# SchematicControlPlotter.net
KiCad netlist of a schematic drawn in EAGLE
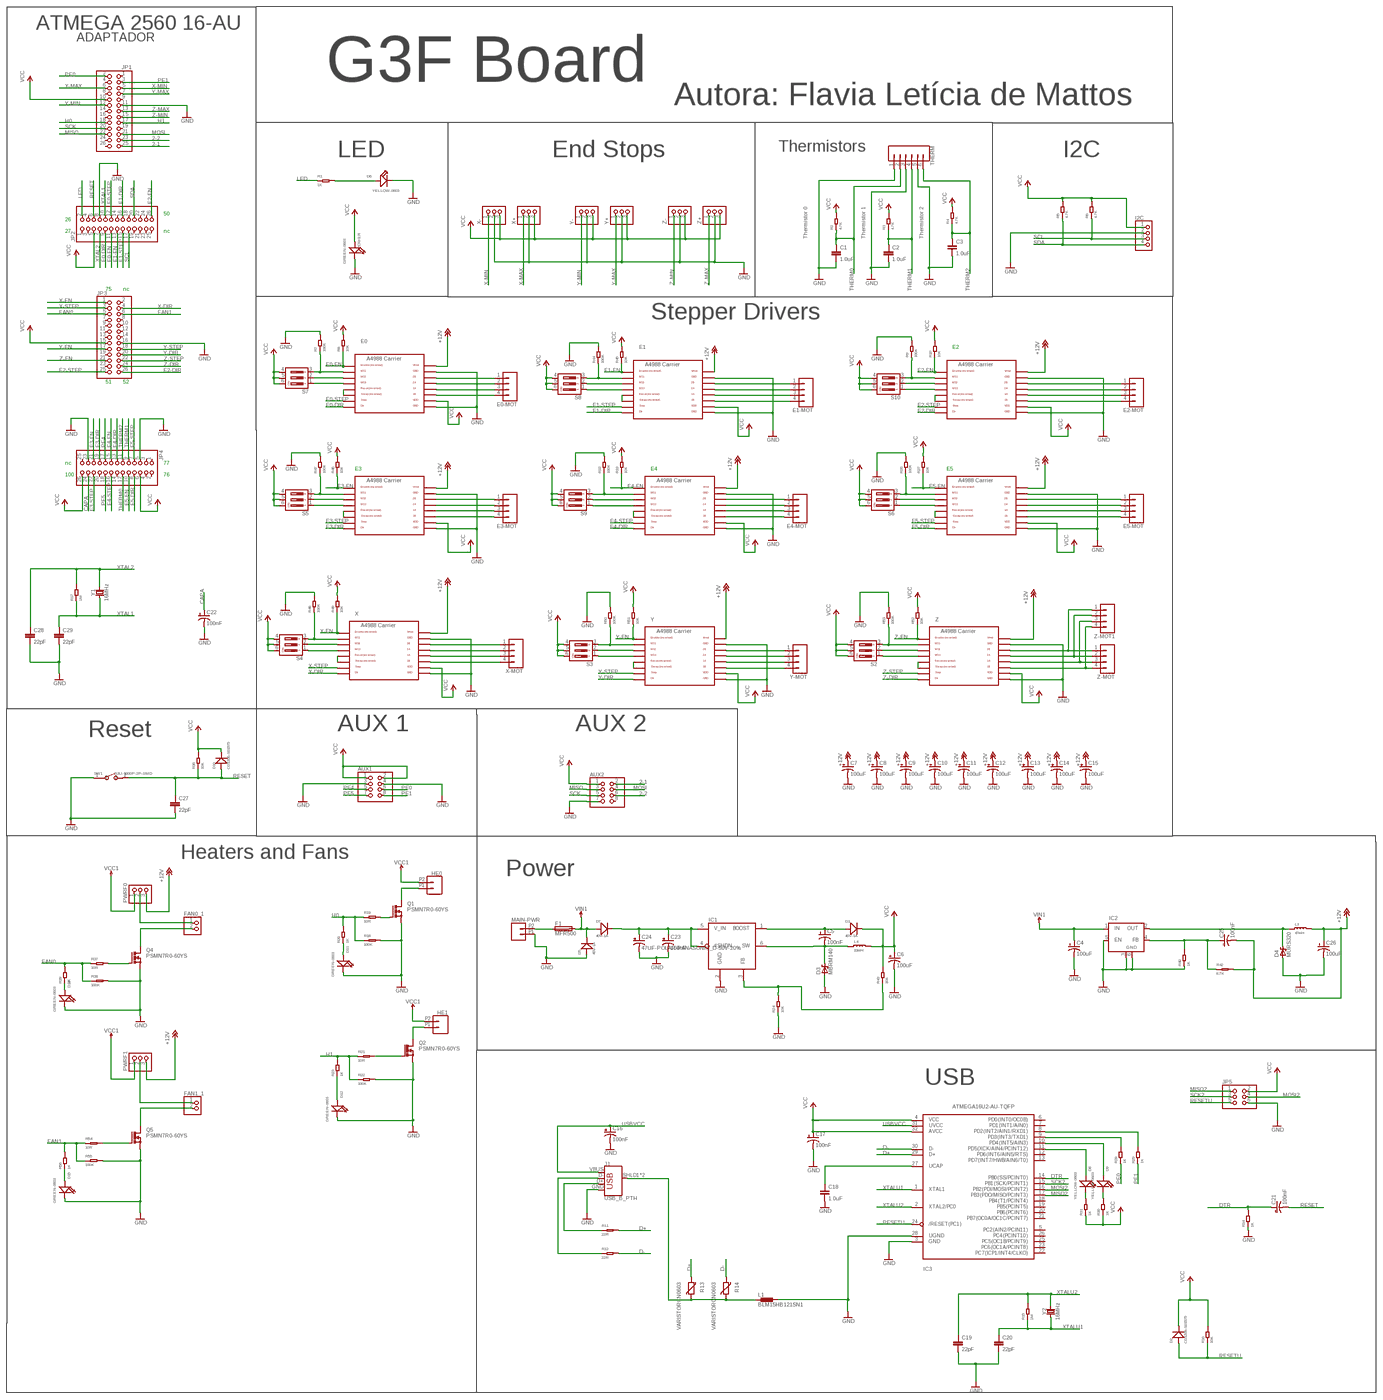
[diagram p0: schematic, sheet 1, overview]
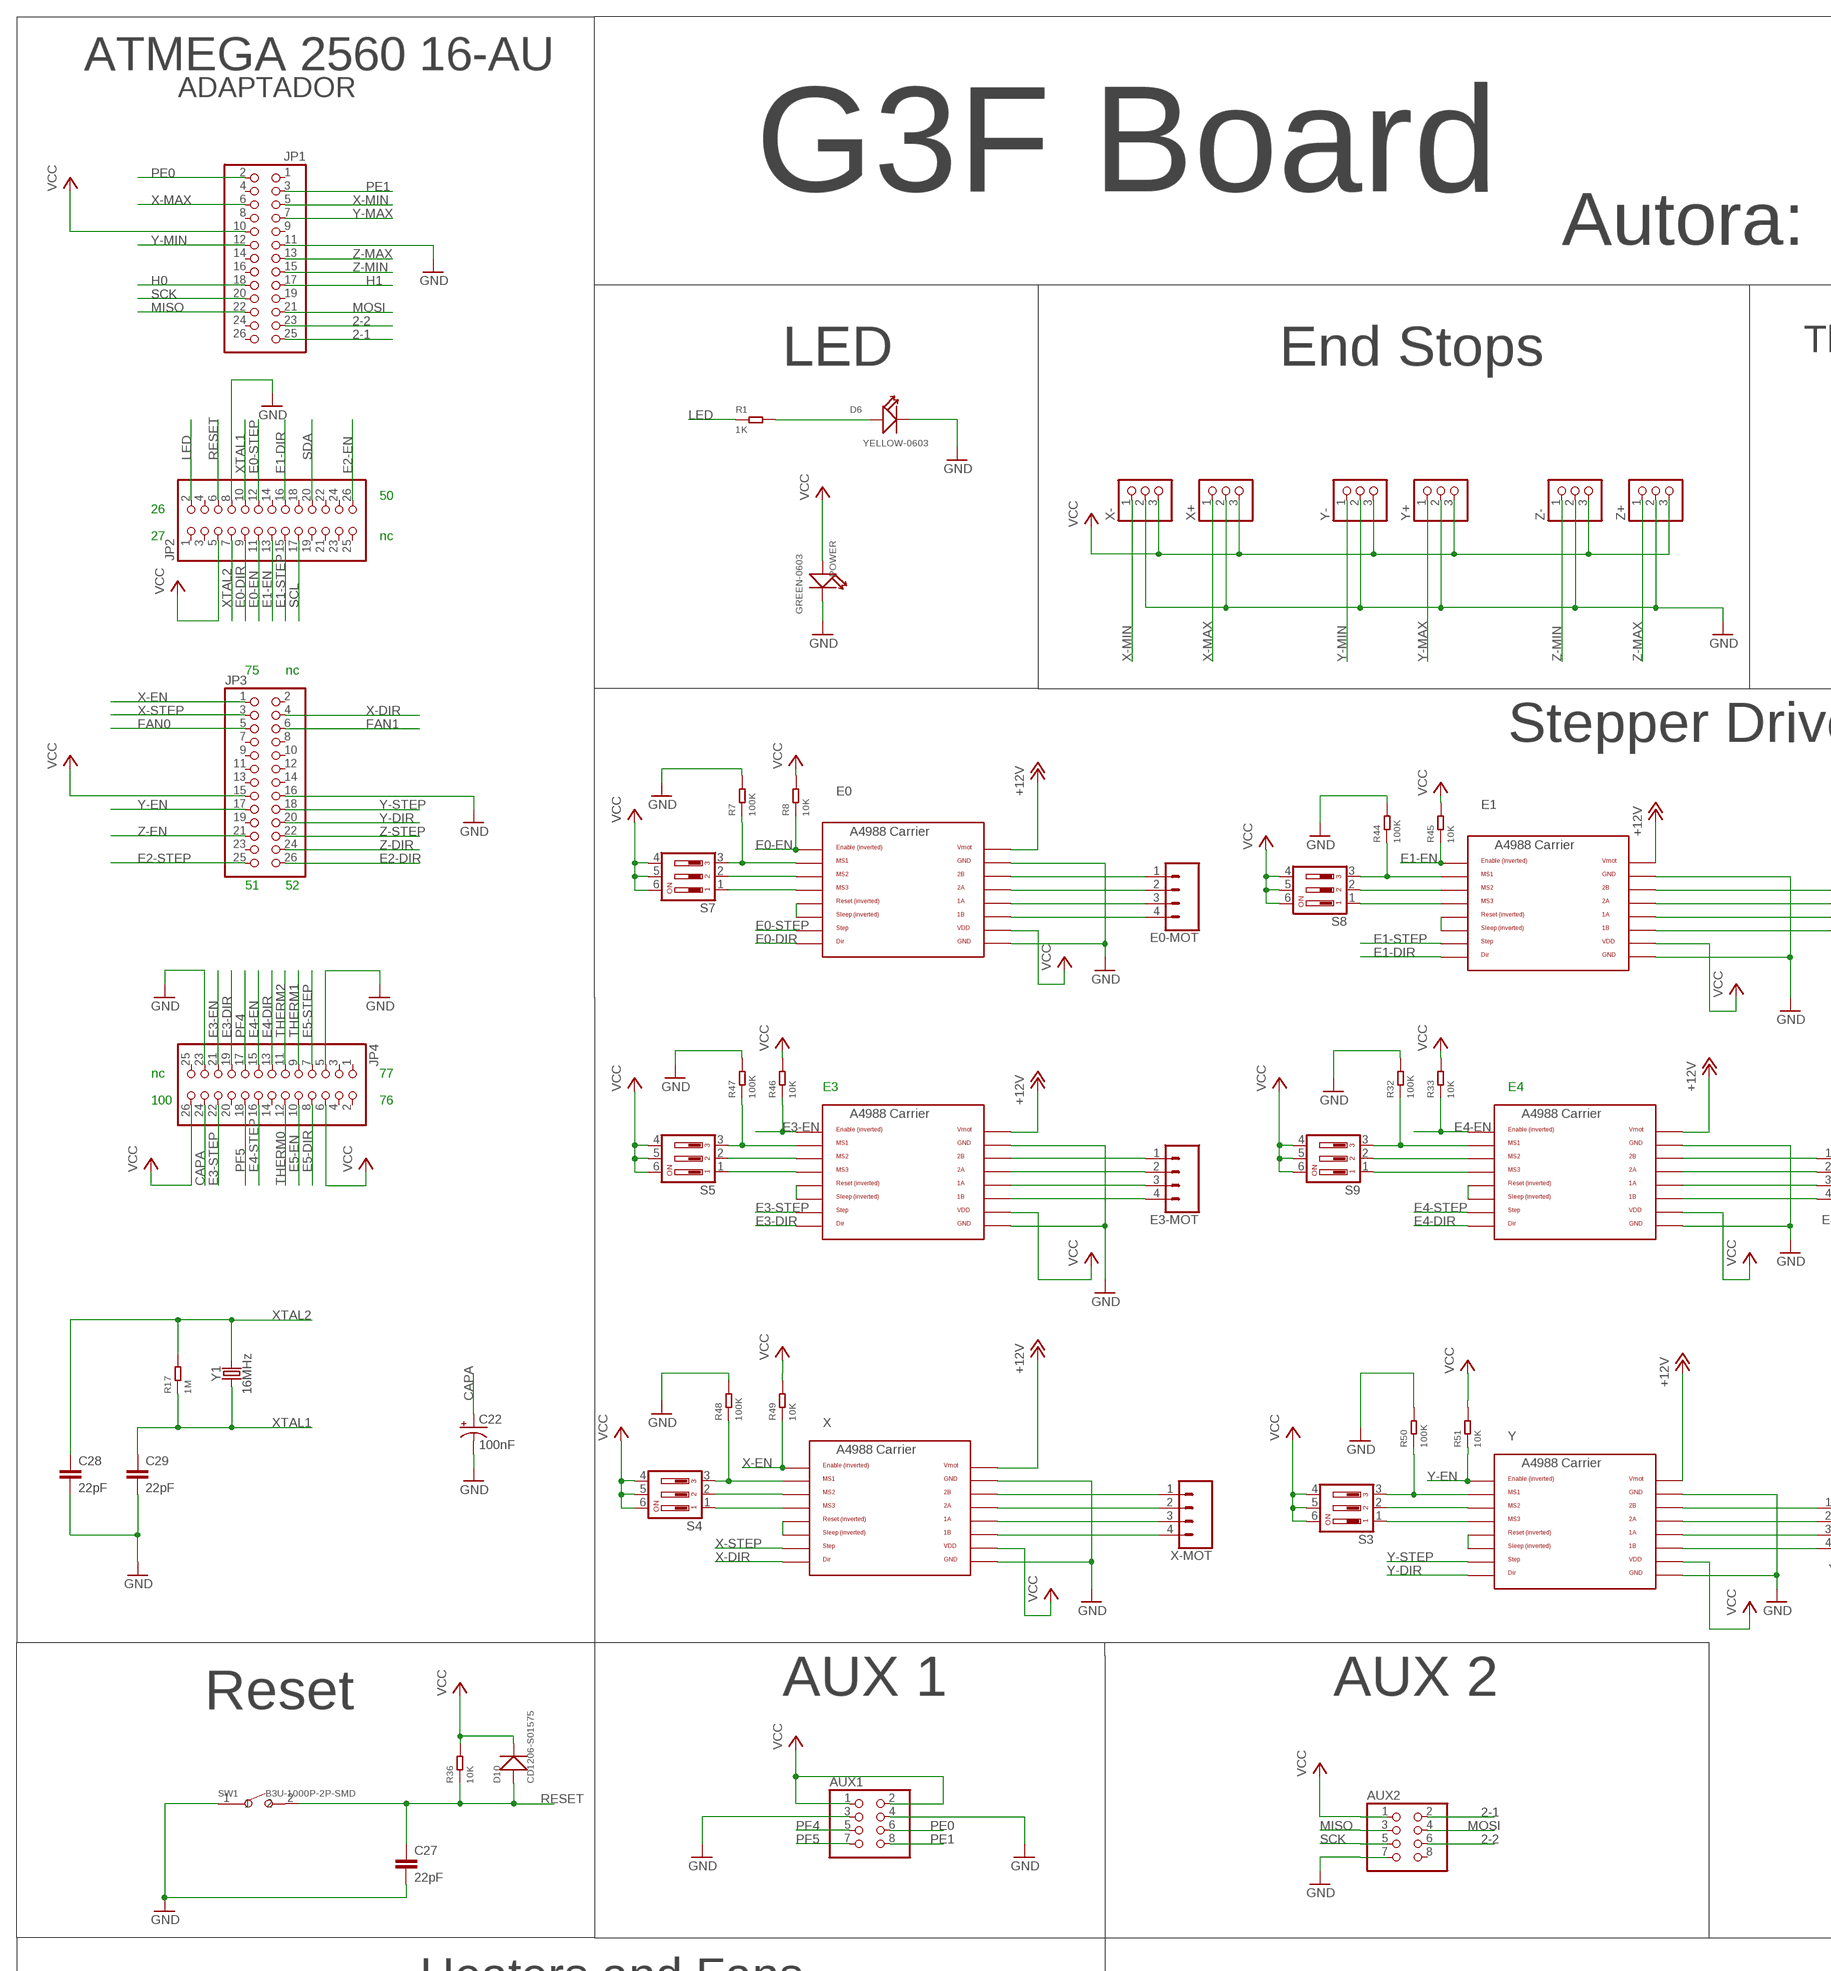
[diagram p1: schematic, sheet 1, part 1 of 4]
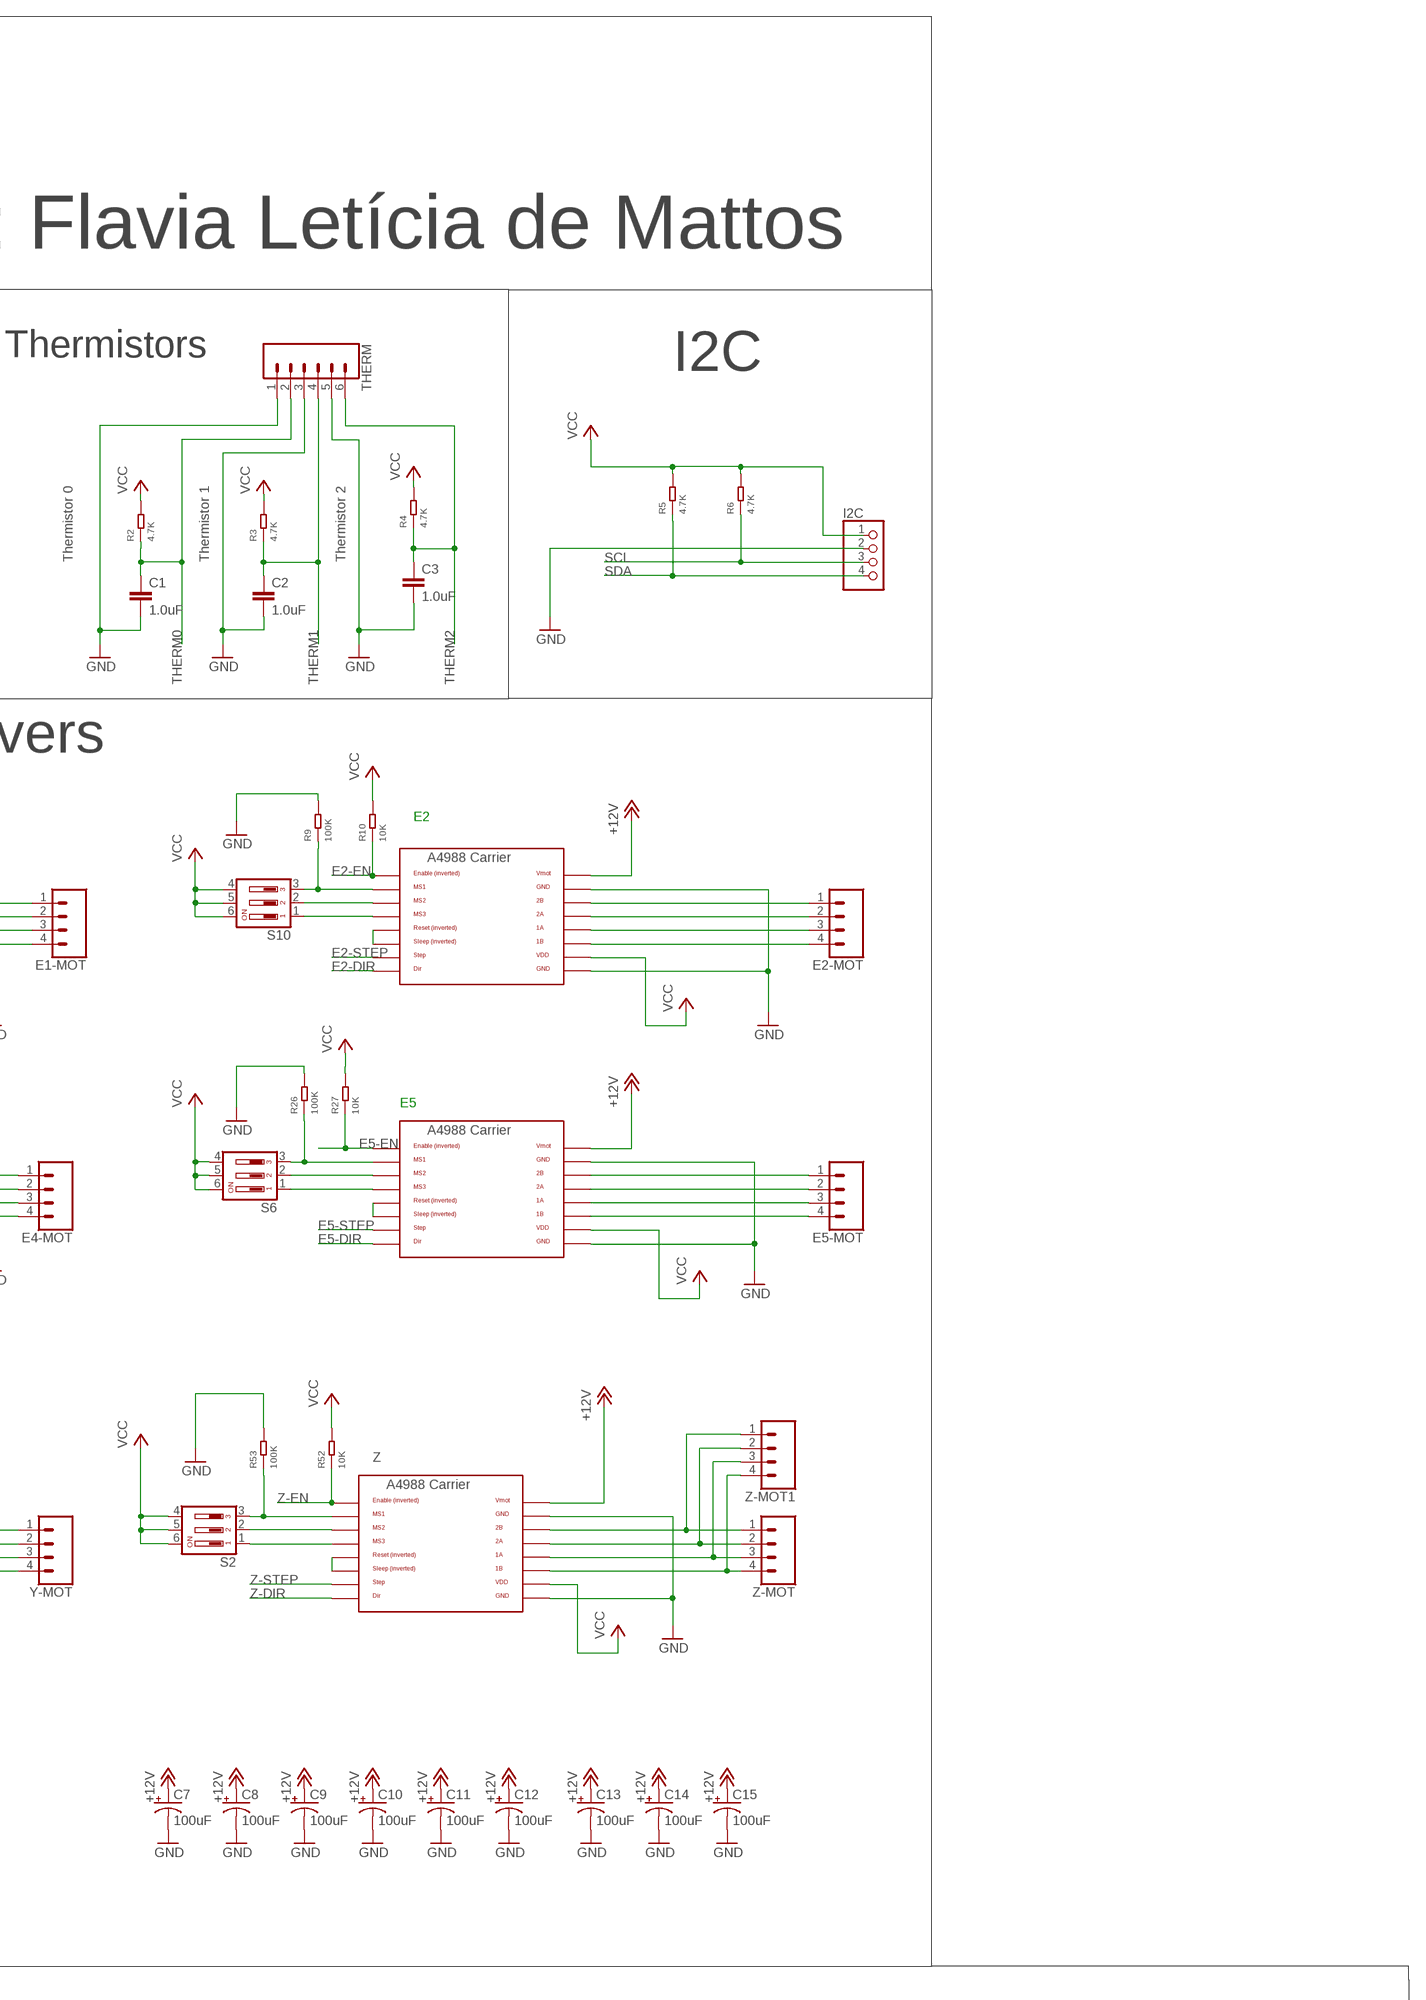
[diagram p2: schematic, sheet 1, part 2 of 4]
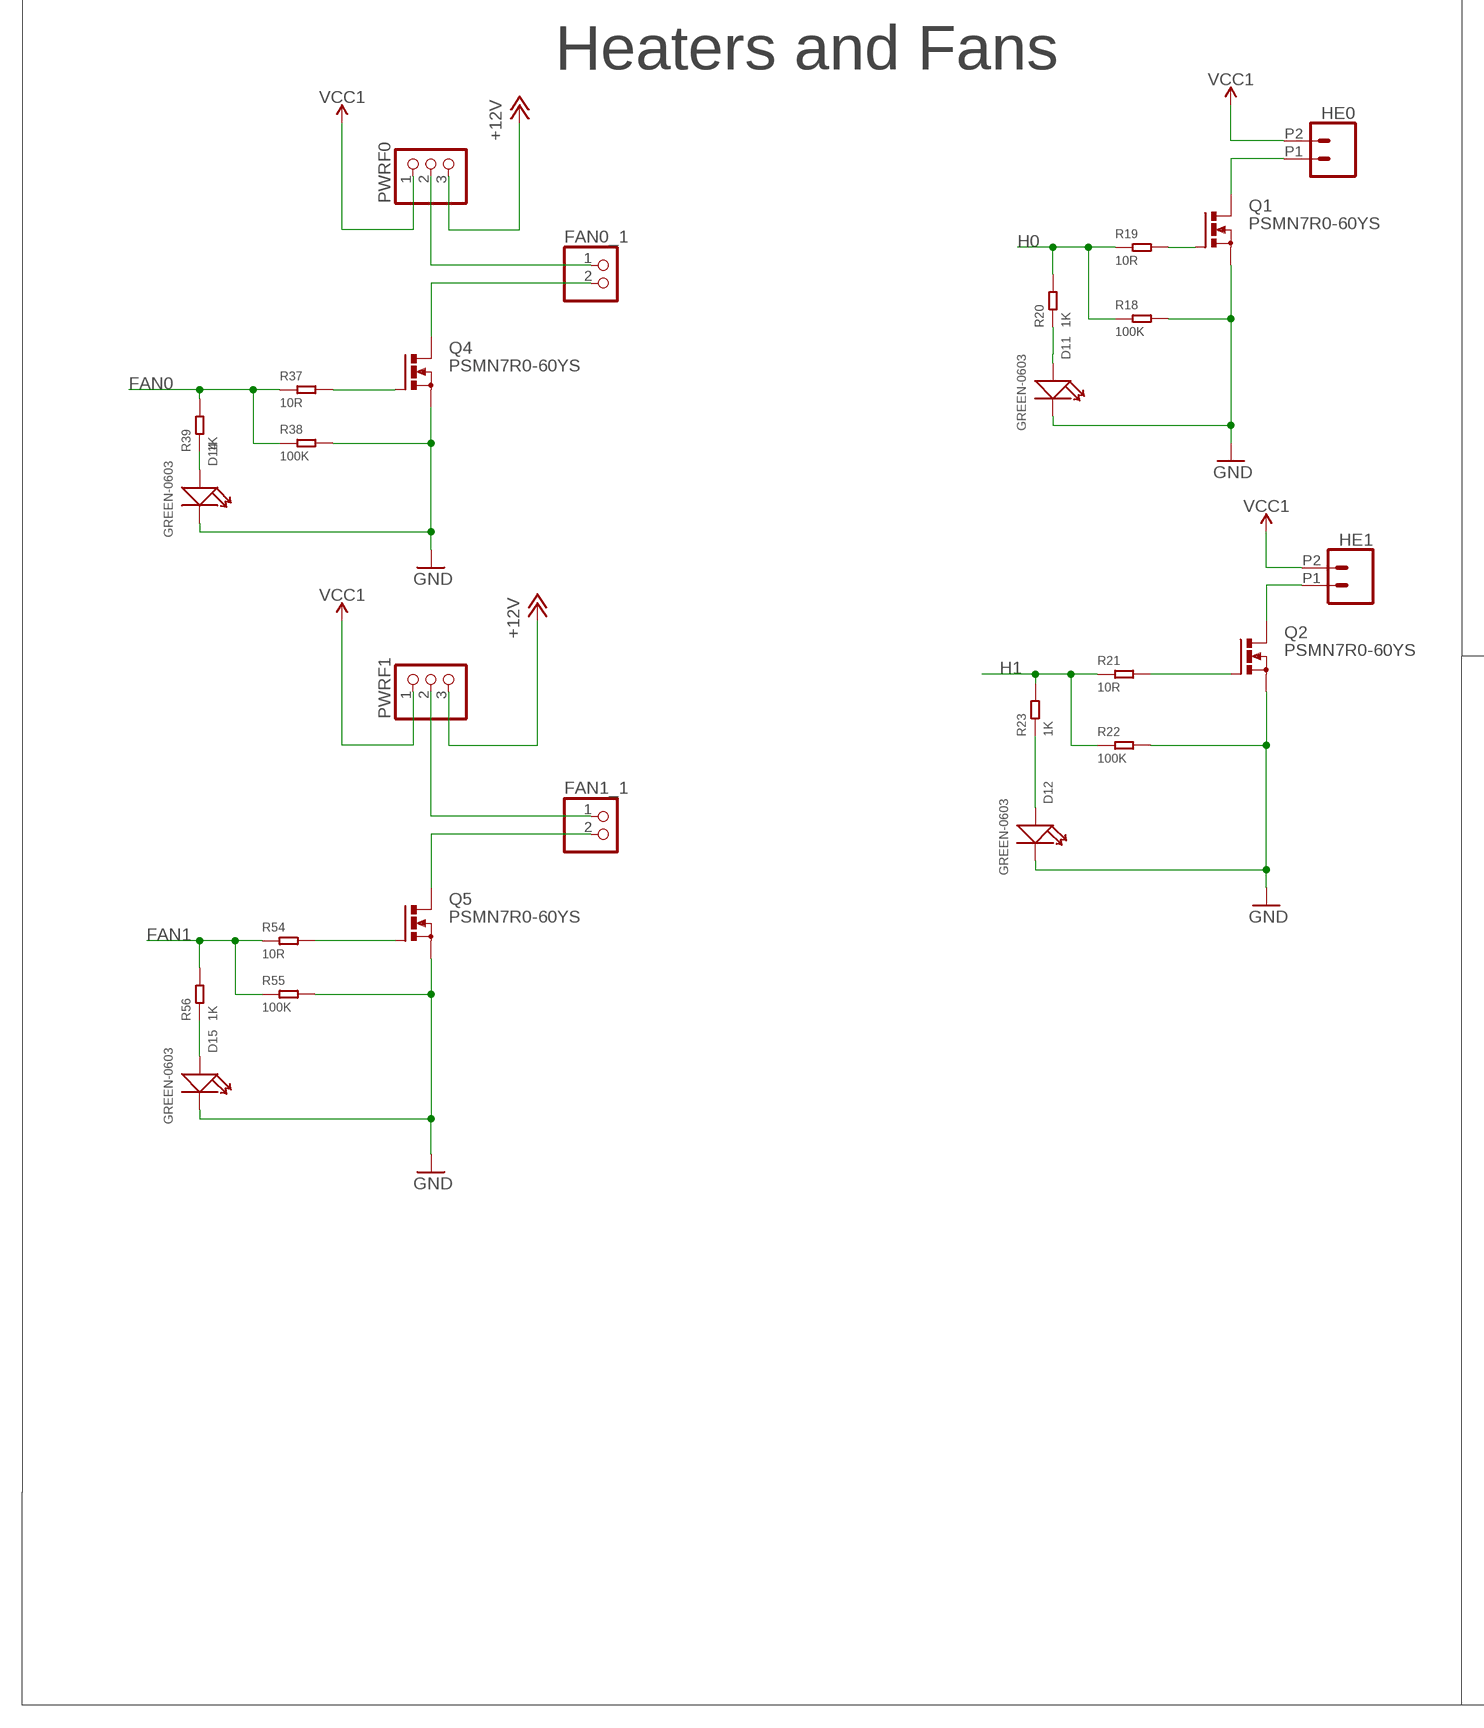
[diagram p3: schematic, sheet 1, part 3 of 4]
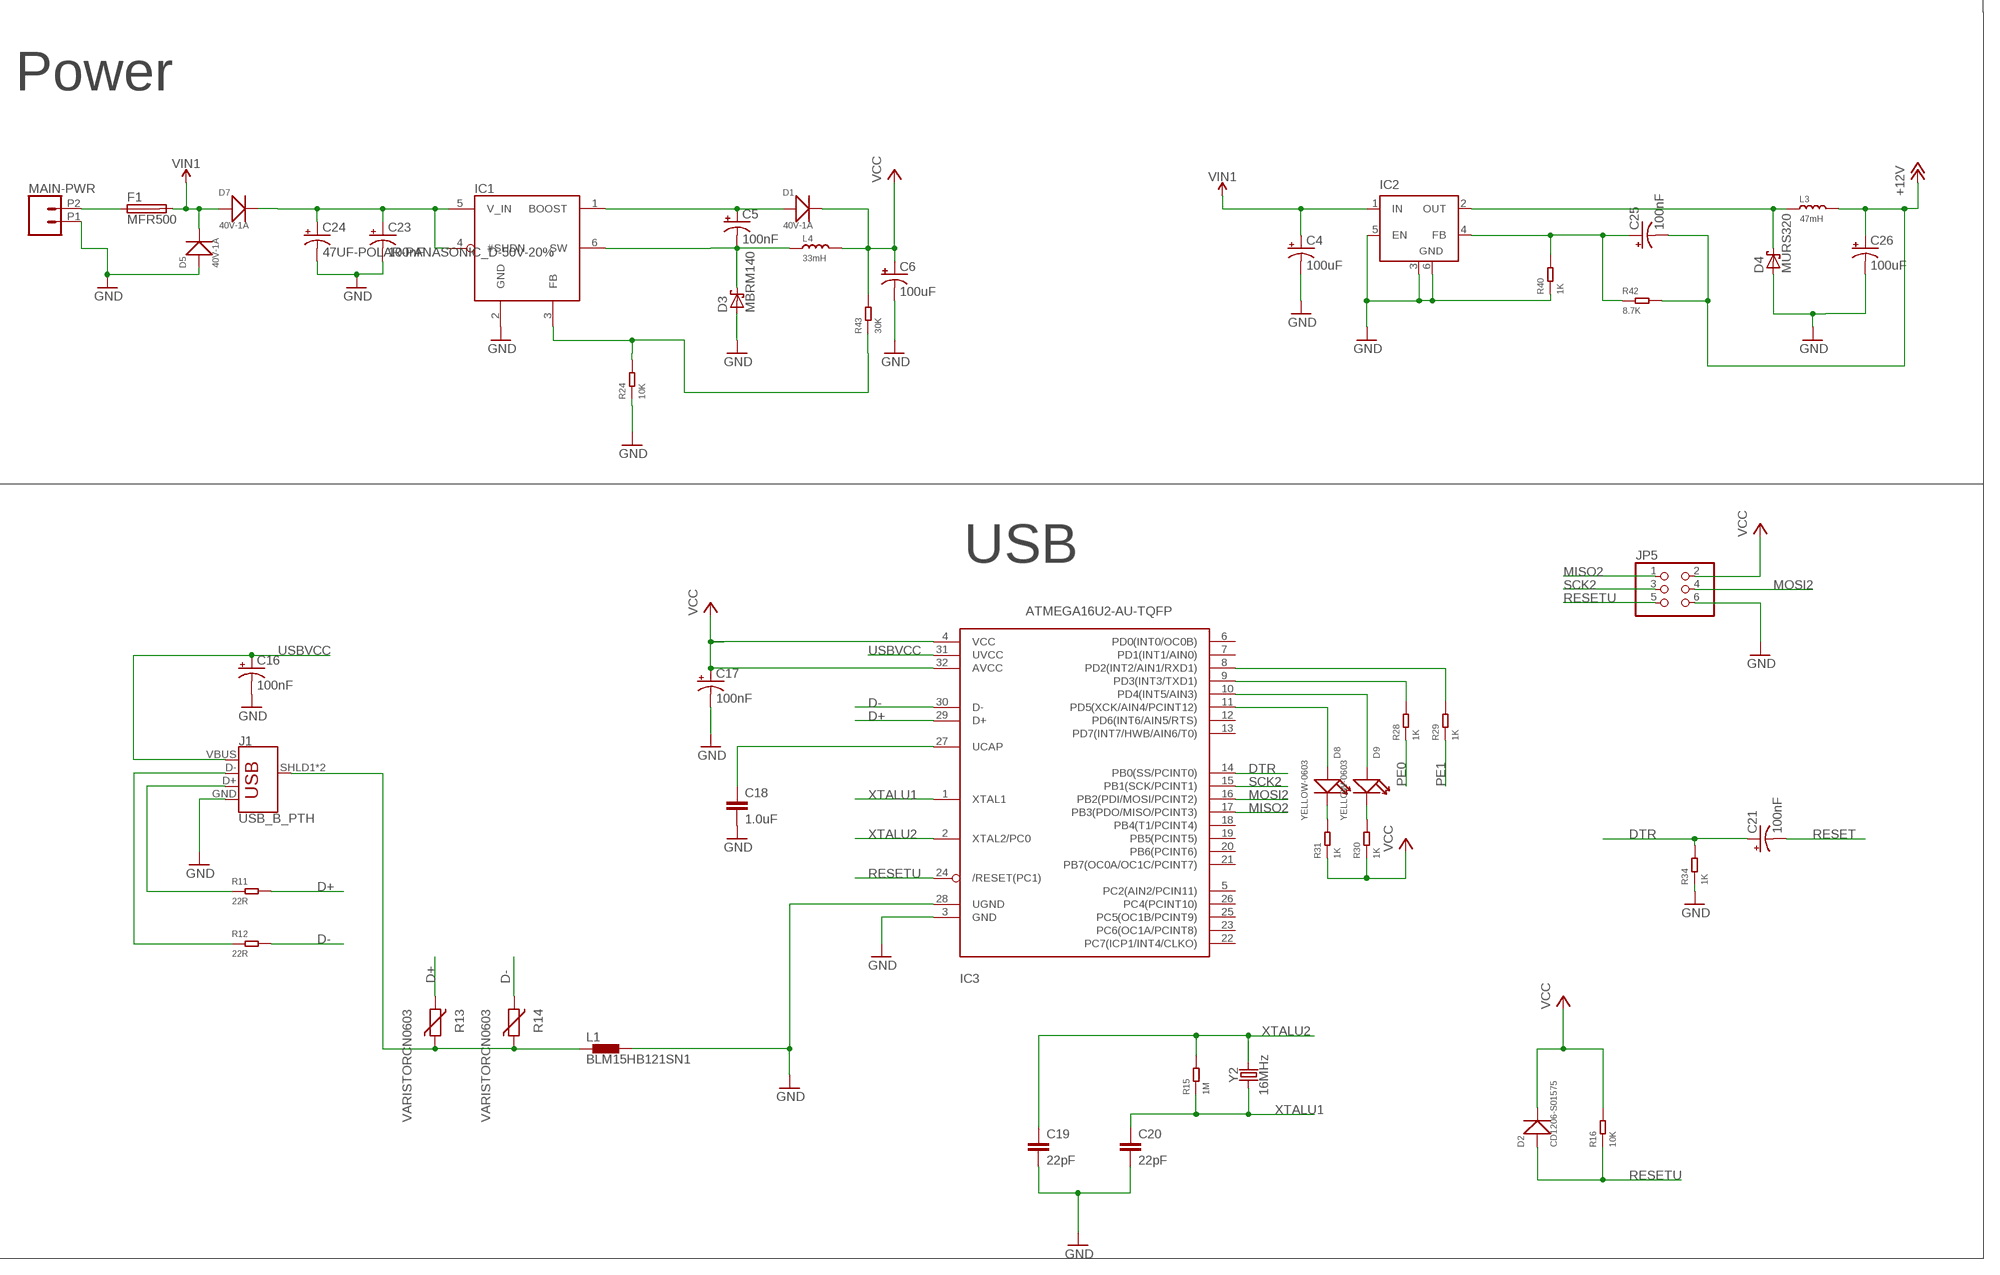
[diagram p4: schematic, sheet 1, part 4 of 4]

(export (version "E")
  (design (tool "Eeschema 10.0.6"))
  (components
    (comp (ref "AUX1")
      (value "PINHD-2X4")
      (footprint "eagle-import:2X04")
      (libsource (lib "eagle-import") (part "PINHD-2X4"))
    )
    (comp (ref "AUX2")
      (value "PINHD-2X4")
      (footprint "eagle-import:2X04")
      (libsource (lib "eagle-import") (part "PINHD-2X4"))
    )
    (comp (ref "C1")
      (value "1.0uF")
      (footprint "eagle-import:0805")
      (libsource (lib "eagle-import") (part "1.0UF-0805-25V-10%"))
    )
    (comp (ref "C2")
      (value "1.0uF")
      (footprint "eagle-import:0805")
      (libsource (lib "eagle-import") (part "1.0UF-0805-25V-10%"))
    )
    (comp (ref "C3")
      (value "1.0uF")
      (footprint "eagle-import:0805")
      (libsource (lib "eagle-import") (part "1.0UF-0805-25V-10%"))
    )
    (comp (ref "C4")
      (value "100uF")
      (footprint "eagle-import:NIC_10X10.5_CAP")
      (libsource (lib "eagle-import") (part "100UF-POLAR-10X10.5-63V-20%"))
    )
    (comp (ref "C5")
      (value "100nF")
      (footprint "eagle-import:NIC_10X10.5_CAP")
      (libsource (lib "eagle-import") (part "100UF-POLAR-10X10.5-63V-20%"))
    )
    (comp (ref "C6")
      (value "100uF")
      (footprint "eagle-import:NIC_10X10.5_CAP")
      (libsource (lib "eagle-import") (part "100UF-POLAR-10X10.5-63V-20%"))
    )
    (comp (ref "C7")
      (value "100uF")
      (footprint "eagle-import:PANASONIC_D")
      (libsource (lib "eagle-import") (part "100UF-POLAR-25V-20%(ELEC)"))
    )
    (comp (ref "C8")
      (value "100uF")
      (footprint "eagle-import:PANASONIC_D")
      (libsource (lib "eagle-import") (part "100UF-POLAR-25V-20%(ELEC)"))
    )
    (comp (ref "C9")
      (value "100uF")
      (footprint "eagle-import:PANASONIC_D")
      (libsource (lib "eagle-import") (part "100UF-POLAR-25V-20%(ELEC)"))
    )
    (comp (ref "C10")
      (value "100uF")
      (footprint "eagle-import:PANASONIC_D")
      (libsource (lib "eagle-import") (part "100UF-POLAR-25V-20%(ELEC)"))
    )
    (comp (ref "C11")
      (value "100uF")
      (footprint "eagle-import:PANASONIC_D")
      (libsource (lib "eagle-import") (part "100UF-POLAR-25V-20%(ELEC)"))
    )
    (comp (ref "C12")
      (value "100uF")
      (footprint "eagle-import:PANASONIC_D")
      (libsource (lib "eagle-import") (part "100UF-POLAR-25V-20%(ELEC)"))
    )
    (comp (ref "C13")
      (value "100uF")
      (footprint "eagle-import:PANASONIC_D")
      (libsource (lib "eagle-import") (part "100UF-POLAR-25V-20%(ELEC)"))
    )
    (comp (ref "C14")
      (value "100uF")
      (footprint "eagle-import:PANASONIC_D")
      (libsource (lib "eagle-import") (part "100UF-POLAR-25V-20%(ELEC)"))
    )
    (comp (ref "C15")
      (value "100uF")
      (footprint "eagle-import:PANASONIC_D")
      (libsource (lib "eagle-import") (part "100UF-POLAR-25V-20%(ELEC)"))
    )
    (comp (ref "C16")
      (value "100nF")
      (footprint "eagle-import:PANASONIC_G")
      (libsource (lib "eagle-import") (part "560UF-PANASONIC_G-25V-20%"))
    )
    (comp (ref "C17")
      (value "100nF")
      (footprint "eagle-import:PANASONIC_G")
      (libsource (lib "eagle-import") (part "560UF-PANASONIC_G-25V-20%"))
    )
    (comp (ref "C18")
      (value "1.0uF")
      (footprint "eagle-import:0603")
      (libsource (lib "eagle-import") (part "1.0UF-0603-16V-10%"))
    )
    (comp (ref "C19")
      (value "22pF")
      (footprint "eagle-import:0603")
      (libsource (lib "eagle-import") (part "22PF-0603-50V-5%"))
    )
    (comp (ref "C20")
      (value "22pF")
      (footprint "eagle-import:0603")
      (libsource (lib "eagle-import") (part "22PF-0603-50V-5%"))
    )
    (comp (ref "C21")
      (value "100nF")
      (footprint "eagle-import:PANASONIC_G")
      (libsource (lib "eagle-import") (part "560UF-PANASONIC_G-25V-20%"))
    )
    (comp (ref "C22")
      (value "100nF")
      (footprint "eagle-import:PANASONIC_G")
      (libsource (lib "eagle-import") (part "560UF-PANASONIC_G-25V-20%"))
    )
    (comp (ref "C23")
      (value "100nF")
      (footprint "eagle-import:PANASONIC_G")
      (libsource (lib "eagle-import") (part "560UF-PANASONIC_G-25V-20%"))
    )
    (comp (ref "C24")
      (value "47UF-POLAR-PANASONIC_D-50V-20%")
      (footprint "eagle-import:PANASONIC_D")
      (libsource (lib "eagle-import") (part "47UF-POLAR-PANASONIC_D-50V-20%"))
    )
    (comp (ref "C25")
      (value "100nF")
      (footprint "eagle-import:NIC_10X10.5_CAP")
      (libsource (lib "eagle-import") (part "100UF-POLAR-10X10.5-63V-20%"))
    )
    (comp (ref "C26")
      (value "100uF")
      (footprint "eagle-import:NIC_10X10.5_CAP")
      (libsource (lib "eagle-import") (part "100UF-POLAR-10X10.5-63V-20%"))
    )
    (comp (ref "C27")
      (value "22pF")
      (footprint "eagle-import:0603")
      (libsource (lib "eagle-import") (part "22PF-0603-50V-5%"))
    )
    (comp (ref "C28")
      (value "22pF")
      (footprint "eagle-import:0603")
      (libsource (lib "eagle-import") (part "22PF-0603-50V-5%"))
    )
    (comp (ref "C29")
      (value "22pF")
      (footprint "eagle-import:0603")
      (libsource (lib "eagle-import") (part "22PF-0603-50V-5%"))
    )
    (comp (ref "D1")
      (value "40V-1A")
      (footprint "eagle-import:DO-214AC")
      (fields (field (name "MPN") "1N5819"))
      (libsource (lib "eagle-import") (part "SMD-DIODE-SCHOTTKY-40V-1A(DO-214AC)"))
    )
    (comp (ref "D2")
      (value "CD1206-S01575")
      (footprint "eagle-import:DO-214AC")
      (fields (field (name "MPN") "1N5819"))
      (libsource (lib "eagle-import") (part "SMD-DIODE-SCHOTTKY-40V-1A(DO-214AC)"))
    )
    (comp (ref "D3")
      (value "MBRM140")
      (footprint "eagle-import:SMB")
      (libsource (lib "eagle-import") (part "SCHOTTKY-DIODESMD"))
    )
    (comp (ref "D4")
      (value "MURS320")
      (footprint "eagle-import:SMB")
      (libsource (lib "eagle-import") (part "SCHOTTKY-DIODESMD"))
    )
    (comp (ref "D5")
      (value "40V-1A")
      (footprint "eagle-import:DO-214AC")
      (fields (field (name "MPN") "1N5819"))
      (libsource (lib "eagle-import") (part "SMD-DIODE-SCHOTTKY-40V-1A(DO-214AC)"))
    )
    (comp (ref "D6")
      (value "YELLOW-0603")
      (footprint "eagle-import:LED-0603")
      (fields (field (name "MPN") "19-217-Y5C-AM1N1VY-3T"))
      (libsource (lib "eagle-import") (part "SMD-LED-CLEAR-YELLOW(0603)"))
    )
    (comp (ref "D7")
      (value "40V-1A")
      (footprint "eagle-import:DO-214AC")
      (fields (field (name "MPN") "1N5819"))
      (libsource (lib "eagle-import") (part "SMD-DIODE-SCHOTTKY-40V-1A(DO-214AC)"))
    )
    (comp (ref "D8")
      (value "YELLOW-0603")
      (footprint "eagle-import:LED-0603")
      (fields (field (name "MPN") "19-217-Y5C-AM1N1VY-3T"))
      (libsource (lib "eagle-import") (part "SMD-LED-CLEAR-YELLOW(0603)"))
    )
    (comp (ref "D9")
      (value "YELLOW-0603")
      (footprint "eagle-import:LED-0603")
      (fields (field (name "MPN") "19-217-Y5C-AM1N1VY-3T"))
      (libsource (lib "eagle-import") (part "SMD-LED-CLEAR-YELLOW(0603)"))
    )
    (comp (ref "D10")
      (value "CD1206-S01575")
      (footprint "eagle-import:DO-214AC")
      (fields (field (name "MPN") "1N5819"))
      (libsource (lib "eagle-import") (part "SMD-DIODE-SCHOTTKY-40V-1A(DO-214AC)"))
    )
    (comp (ref "D11")
      (value "GREEN-0603")
      (footprint "eagle-import:LED-0603")
      (fields (field (name "MPN") "19-217-G7C-AN1P2-3T"))
      (libsource (lib "eagle-import") (part "SMD-LED-CLEAR-GREEN(0603)"))
    )
    (comp (ref "D12")
      (value "GREEN-0603")
      (footprint "eagle-import:LED-0603")
      (fields (field (name "MPN") "19-217-G7C-AN1P2-3T"))
      (libsource (lib "eagle-import") (part "SMD-LED-CLEAR-GREEN(0603)"))
    )
    (comp (ref "D14")
      (value "GREEN-0603")
      (footprint "eagle-import:LED-0603")
      (fields (field (name "MPN") "19-217-G7C-AN1P2-3T"))
      (libsource (lib "eagle-import") (part "SMD-LED-CLEAR-GREEN(0603)"))
    )
    (comp (ref "D15")
      (value "GREEN-0603")
      (footprint "eagle-import:LED-0603")
      (fields (field (name "MPN") "19-217-G7C-AN1P2-3T"))
      (libsource (lib "eagle-import") (part "SMD-LED-CLEAR-GREEN(0603)"))
    )
    (comp (ref "E0-MOT")
      (value "CONN_04SCREW_LOCK")
      (footprint "eagle-import:SCREWTERMINAL-3.5MM-4_LOCK")
      (libsource (lib "eagle-import") (part "CONN_04SCREW_LOCK"))
    )
    (comp (ref "E1-MOT")
      (value "CONN_04SCREW_LOCK")
      (footprint "eagle-import:SCREWTERMINAL-3.5MM-4_LOCK")
      (libsource (lib "eagle-import") (part "CONN_04SCREW_LOCK"))
    )
    (comp (ref "E2-MOT")
      (value "CONN_04SCREW_LOCK")
      (footprint "eagle-import:SCREWTERMINAL-3.5MM-4_LOCK")
      (libsource (lib "eagle-import") (part "CONN_04SCREW_LOCK"))
    )
    (comp (ref "E3-MOT")
      (value "CONN_04SCREW_LOCK")
      (footprint "eagle-import:SCREWTERMINAL-3.5MM-4_LOCK")
      (libsource (lib "eagle-import") (part "CONN_04SCREW_LOCK"))
    )
    (comp (ref "E4-MOT")
      (value "CONN_04SCREW_LOCK")
      (footprint "eagle-import:SCREWTERMINAL-3.5MM-4_LOCK")
      (libsource (lib "eagle-import") (part "CONN_04SCREW_LOCK"))
    )
    (comp (ref "E5-MOT")
      (value "CONN_04SCREW_LOCK")
      (footprint "eagle-import:SCREWTERMINAL-3.5MM-4_LOCK")
      (libsource (lib "eagle-import") (part "CONN_04SCREW_LOCK"))
    )
    (comp (ref "F1")
      (value "MFR500")
      (footprint "eagle-import:LITTLEFUSE")
      (libsource (lib "eagle-import") (part "FUSELITTLEFUSE"))
    )
    (comp (ref "FAN0_1")
      (value "PINHD-1X2")
      (footprint "eagle-import:1X02")
      (libsource (lib "eagle-import") (part "PINHD-1X2"))
    )
    (comp (ref "FAN1_1")
      (value "PINHD-1X2")
      (footprint "eagle-import:1X02")
      (libsource (lib "eagle-import") (part "PINHD-1X2"))
    )
    (comp (ref "HE0")
      (value "CONN_022.54MM_SCREWTERM")
      (footprint "eagle-import:1X02_2.54_SCREWTERM")
      (libsource (lib "eagle-import") (part "CONN_022.54MM_SCREWTERM"))
    )
    (comp (ref "HE1")
      (value "CONN_022.54MM_SCREWTERM")
      (footprint "eagle-import:1X02_2.54_SCREWTERM")
      (libsource (lib "eagle-import") (part "CONN_022.54MM_SCREWTERM"))
    )
    (comp (ref "I2C")
      (value "PINHD-1X4")
      (footprint "eagle-import:1X04")
      (libsource (lib "eagle-import") (part "PINHD-1X4"))
    )
    (comp (ref "IC1")
      (value "LT1933ES6")
      (footprint "eagle-import:SOT23-6")
      (libsource (lib "eagle-import") (part "LT1933ES6"))
    )
    (comp (ref "IC2")
      (value "LM2596S")
      (footprint "eagle-import:TO263-5")
      (libsource (lib "eagle-import") (part "LM2596S"))
    )
    (comp (ref "IC3")
      (value "ATMEGA16U2-AU-TQFP")
      (footprint "eagle-import:TQFP32-08")
      (libsource (lib "eagle-import") (part "ATMEGA16U2-AU-TQFP"))
    )
    (comp (ref "J1")
      (value "USB_B_PTH")
      (footprint "eagle-import:USB-B-PTH")
      (libsource (lib "eagle-import") (part "USB_B_PTH"))
    )
    (comp (ref "JP1")
      (value "PINHD-2X13")
      (footprint "eagle-import:2X13")
      (libsource (lib "eagle-import") (part "PINHD-2X13"))
    )
    (comp (ref "JP2")
      (value "PINHD-2X13")
      (footprint "eagle-import:2X13")
      (libsource (lib "eagle-import") (part "PINHD-2X13"))
    )
    (comp (ref "JP3")
      (value "PINHD-2X13")
      (footprint "eagle-import:2X13")
      (libsource (lib "eagle-import") (part "PINHD-2X13"))
    )
    (comp (ref "JP4")
      (value "PINHD-2X13")
      (footprint "eagle-import:2X13")
      (libsource (lib "eagle-import") (part "PINHD-2X13"))
    )
    (comp (ref "JP5")
      (value "PINHD-2X3")
      (footprint "eagle-import:2X03")
      (libsource (lib "eagle-import") (part "PINHD-2X3"))
    )
    (comp (ref "L1")
      (value "BLM15HB121SN1")
      (footprint "eagle-import:0402")
      (libsource (lib "eagle-import") (part "BLM15HB121SN1"))
    )
    (comp (ref "L3")
      (value "47mH")
      (footprint "eagle-import:L0402")
      (fields (field (name "MPN") "LQG15HS4N7S02"))
      (libsource (lib "eagle-import") (part "SMD-INDUCTOR-4.7NH-0.3NH-300MA(0402)"))
    )
    (comp (ref "L4")
      (value "33mH")
      (footprint "eagle-import:L0402")
      (libsource (lib "eagle-import") (part "SMD-INDUCTOR-3.3NH-0.3NH-300MA(0402)"))
    )
    (comp (ref "MAIN-PWR")
      (value "CONN_022.54MM_SCREWTERM")
      (footprint "eagle-import:1X02_2.54_SCREWTERM")
      (libsource (lib "eagle-import") (part "CONN_022.54MM_SCREWTERM"))
    )
    (comp (ref "POWER")
      (value "GREEN-0603")
      (footprint "eagle-import:LED-0603")
      (fields (field (name "MPN") "19-217-G7C-AN1P2-3T"))
      (libsource (lib "eagle-import") (part "SMD-LED-CLEAR-GREEN(0603)"))
    )
    (comp (ref "PWRF0")
      (value "PINHD-1X3")
      (footprint "eagle-import:1X03")
      (libsource (lib "eagle-import") (part "PINHD-1X3"))
    )
    (comp (ref "PWRF1")
      (value "PINHD-1X3")
      (footprint "eagle-import:1X03")
      (libsource (lib "eagle-import") (part "PINHD-1X3"))
    )
    (comp (ref "Q1")
      (value "PSMN7R0-60YS")
      (footprint "eagle-import:TO220BH")
      (libsource (lib "eagle-import") (part "PMOSFET_NTO220BH"))
    )
    (comp (ref "Q2")
      (value "PSMN7R0-60YS")
      (footprint "eagle-import:TO220BH")
      (libsource (lib "eagle-import") (part "PMOSFET_NTO220BH"))
    )
    (comp (ref "Q4")
      (value "PSMN7R0-60YS")
      (footprint "eagle-import:TO220BH")
      (libsource (lib "eagle-import") (part "PMOSFET_NTO220BH"))
    )
    (comp (ref "Q5")
      (value "PSMN7R0-60YS")
      (footprint "eagle-import:TO220BH")
      (libsource (lib "eagle-import") (part "PMOSFET_NTO220BH"))
    )
    (comp (ref "R1")
      (value "1K")
      (footprint "eagle-import:R0603")
      (fields (field (name "MPN") "RC0603FR-071KL"))
      (libsource (lib "eagle-import") (part "SMD-RES-1K-1%-1/10W(0603)"))
    )
    (comp (ref "R2")
      (value "4.7K")
      (footprint "eagle-import:R0603")
      (fields (field (name "MPN") "RC0603JR-074K7L"))
      (libsource (lib "eagle-import") (part "SMD-RES-4.7K-5%-1/10W(0603)"))
    )
    (comp (ref "R3")
      (value "4.7K")
      (footprint "eagle-import:R0603")
      (fields (field (name "MPN") "RC0603JR-074K7L"))
      (libsource (lib "eagle-import") (part "SMD-RES-4.7K-5%-1/10W(0603)"))
    )
    (comp (ref "R4")
      (value "4.7K")
      (footprint "eagle-import:R0603")
      (fields (field (name "MPN") "RC0603JR-074K7L"))
      (libsource (lib "eagle-import") (part "SMD-RES-4.7K-5%-1/10W(0603)"))
    )
    (comp (ref "R5")
      (value "4.7K")
      (footprint "eagle-import:R0603")
      (fields (field (name "MPN") "RC0603JR-074K7L"))
      (libsource (lib "eagle-import") (part "SMD-RES-4.7K-5%-1/10W(0603)"))
    )
    (comp (ref "R6")
      (value "4.7K")
      (footprint "eagle-import:R0603")
      (fields (field (name "MPN") "RC0603JR-074K7L"))
      (libsource (lib "eagle-import") (part "SMD-RES-4.7K-5%-1/10W(0603)"))
    )
    (comp (ref "R7")
      (value "100K")
      (footprint "eagle-import:R0603")
      (fields (field (name "MPN") "RC0603FR-07100KL"))
      (libsource (lib "eagle-import") (part "SMD-RES-100K-1%-1/10W(0603)"))
    )
    (comp (ref "R8")
      (value "10K")
      (footprint "eagle-import:R0603")
      (fields (field (name "MPN") "RC0603FR-0710KL"))
      (libsource (lib "eagle-import") (part "SMD-RES-10K-1%-1/10W(0603)"))
    )
    (comp (ref "R9")
      (value "100K")
      (footprint "eagle-import:R0603")
      (fields (field (name "MPN") "RC0603FR-07100KL"))
      (libsource (lib "eagle-import") (part "SMD-RES-100K-1%-1/10W(0603)"))
    )
    (comp (ref "R10")
      (value "10K")
      (footprint "eagle-import:R0603")
      (fields (field (name "MPN") "RC0603FR-0710KL"))
      (libsource (lib "eagle-import") (part "SMD-RES-10K-1%-1/10W(0603)"))
    )
    (comp (ref "R11")
      (value "22R")
      (footprint "eagle-import:R0603")
      (fields (field (name "MPN") "RC0603JR-0722RL"))
      (libsource (lib "eagle-import") (part "SMD-RES-22R-5%-1/10W(0603)"))
    )
    (comp (ref "R12")
      (value "22R")
      (footprint "eagle-import:R0603")
      (fields (field (name "MPN") "RC0603JR-0722RL"))
      (libsource (lib "eagle-import") (part "SMD-RES-22R-5%-1/10W(0603)"))
    )
    (comp (ref "R13")
      (value "VARISTORCN0603")
      (footprint "eagle-import:CT_CN0603")
      (libsource (lib "eagle-import") (part "VARISTORCN0603"))
    )
    (comp (ref "R14")
      (value "VARISTORCN0603")
      (footprint "eagle-import:CT_CN0603")
      (libsource (lib "eagle-import") (part "VARISTORCN0603"))
    )
    (comp (ref "R15")
      (value "1M")
      (footprint "eagle-import:R0603")
      (fields (field (name "MPN") "RC0603FR-0710ML"))
      (libsource (lib "eagle-import") (part "SMD-RES-10M-1%-1/10W(0603)"))
    )
    (comp (ref "R16")
      (value "10K")
      (footprint "eagle-import:R0603")
      (fields (field (name "MPN") "RC0603FR-0710KL"))
      (libsource (lib "eagle-import") (part "SMD-RES-10K-1%-1/10W(0603)"))
    )
    (comp (ref "R17")
      (value "1M")
      (footprint "eagle-import:R0603")
      (fields (field (name "MPN") "RC0603FR-0710ML"))
      (libsource (lib "eagle-import") (part "SMD-RES-10M-1%-1/10W(0603)"))
    )
    (comp (ref "R18")
      (value "100K")
      (footprint "eagle-import:R0603")
      (fields (field (name "MPN") "RC0603FR-07100KL"))
      (libsource (lib "eagle-import") (part "SMD-RES-100K-1%-1/10W(0603)"))
    )
    (comp (ref "R19")
      (value "10R")
      (footprint "eagle-import:R0603")
      (fields (field (name "MPN") "RC0603FR-0710RL"))
      (libsource (lib "eagle-import") (part "SMD-RES-10R-1%-1/10W(0603)"))
    )
    (comp (ref "R20")
      (value "1K")
      (footprint "eagle-import:R0603")
      (fields (field (name "MPN") "RC0603FR-071KL"))
      (libsource (lib "eagle-import") (part "SMD-RES-1K-1%-1/10W(0603)"))
    )
    (comp (ref "R21")
      (value "10R")
      (footprint "eagle-import:R0603")
      (fields (field (name "MPN") "RC0603FR-0710RL"))
      (libsource (lib "eagle-import") (part "SMD-RES-10R-1%-1/10W(0603)"))
    )
    (comp (ref "R22")
      (value "100K")
      (footprint "eagle-import:R0603")
      (fields (field (name "MPN") "RC0603FR-07100KL"))
      (libsource (lib "eagle-import") (part "SMD-RES-100K-1%-1/10W(0603)"))
    )
    (comp (ref "R23")
      (value "1K")
      (footprint "eagle-import:R0603")
      (fields (field (name "MPN") "RC0603FR-071KL"))
      (libsource (lib "eagle-import") (part "SMD-RES-1K-1%-1/10W(0603)"))
    )
    (comp (ref "R24")
      (value "10K")
      (footprint "eagle-import:R0603")
      (fields (field (name "MPN") "RC0603FR-0710KL"))
      (libsource (lib "eagle-import") (part "SMD-RES-10K-1%-1/10W(0603)"))
    )
    (comp (ref "R26")
      (value "100K")
      (footprint "eagle-import:R0603")
      (fields (field (name "MPN") "RC0603FR-07100KL"))
      (libsource (lib "eagle-import") (part "SMD-RES-100K-1%-1/10W(0603)"))
    )
    (comp (ref "R27")
      (value "10K")
      (footprint "eagle-import:R0603")
      (fields (field (name "MPN") "RC0603FR-0710KL"))
      (libsource (lib "eagle-import") (part "SMD-RES-10K-1%-1/10W(0603)"))
    )
    (comp (ref "R28")
      (value "1K")
      (footprint "eagle-import:R0603")
      (fields (field (name "MPN") "RC0603FR-071KL"))
      (libsource (lib "eagle-import") (part "SMD-RES-1K-1%-1/10W(0603)"))
    )
    (comp (ref "R29")
      (value "1K")
      (footprint "eagle-import:R0603")
      (fields (field (name "MPN") "RC0603FR-071KL"))
      (libsource (lib "eagle-import") (part "SMD-RES-1K-1%-1/10W(0603)"))
    )
    (comp (ref "R30")
      (value "1K")
      (footprint "eagle-import:R0603")
      (fields (field (name "MPN") "RC0603FR-071KL"))
      (libsource (lib "eagle-import") (part "SMD-RES-1K-1%-1/10W(0603)"))
    )
    (comp (ref "R31")
      (value "1K")
      (footprint "eagle-import:R0603")
      (fields (field (name "MPN") "RC0603FR-071KL"))
      (libsource (lib "eagle-import") (part "SMD-RES-1K-1%-1/10W(0603)"))
    )
    (comp (ref "R32")
      (value "100K")
      (footprint "eagle-import:R0603")
      (fields (field (name "MPN") "RC0603FR-07100KL"))
      (libsource (lib "eagle-import") (part "SMD-RES-100K-1%-1/10W(0603)"))
    )
    (comp (ref "R33")
      (value "10K")
      (footprint "eagle-import:R0603")
      (fields (field (name "MPN") "RC0603FR-0710KL"))
      (libsource (lib "eagle-import") (part "SMD-RES-10K-1%-1/10W(0603)"))
    )
    (comp (ref "R34")
      (value "1K")
      (footprint "eagle-import:R0603")
      (fields (field (name "MPN") "RC0603FR-071KL"))
      (libsource (lib "eagle-import") (part "SMD-RES-1K-1%-1/10W(0603)"))
    )
    (comp (ref "R36")
      (value "10K")
      (footprint "eagle-import:R0603")
      (fields (field (name "MPN") "RC0603FR-0710KL"))
      (libsource (lib "eagle-import") (part "SMD-RES-10K-1%-1/10W(0603)"))
    )
    (comp (ref "R37")
      (value "10R")
      (footprint "eagle-import:R0603")
      (fields (field (name "MPN") "RC0603FR-0710RL"))
      (libsource (lib "eagle-import") (part "SMD-RES-10R-1%-1/10W(0603)"))
    )
    (comp (ref "R38")
      (value "100K")
      (footprint "eagle-import:R0603")
      (fields (field (name "MPN") "RC0603FR-07100KL"))
      (libsource (lib "eagle-import") (part "SMD-RES-100K-1%-1/10W(0603)"))
    )
    (comp (ref "R39")
      (value "1K")
      (footprint "eagle-import:R0603")
      (fields (field (name "MPN") "RC0603FR-071KL"))
      (libsource (lib "eagle-import") (part "SMD-RES-1K-1%-1/10W(0603)"))
    )
    (comp (ref "R40")
      (value "1K")
      (footprint "eagle-import:R0805")
      (fields (field (name "MPN") "RC0805JR-071KL"))
      (libsource (lib "eagle-import") (part "SMD-RES-1K-5%-1/8W(0805)"))
    )
    (comp (ref "R42")
      (value "8.7K")
      (footprint "eagle-import:R0805")
      (fields (field (name "MPN") "RC0805JR-074K7L"))
      (libsource (lib "eagle-import") (part "SMD-RES-4.7K-5%-1/8W(0805)"))
    )
    (comp (ref "R43")
      (value "30K")
      (footprint "eagle-import:R0603")
      (fields (field (name "MPN") "RC0603FR-0730KL"))
      (libsource (lib "eagle-import") (part "SMD-RES-30K-1%-1/10W(0603)"))
    )
    (comp (ref "R44")
      (value "100K")
      (footprint "eagle-import:R0603")
      (fields (field (name "MPN") "RC0603FR-07100KL"))
      (libsource (lib "eagle-import") (part "SMD-RES-100K-1%-1/10W(0603)"))
    )
    (comp (ref "R45")
      (value "10K")
      (footprint "eagle-import:R0603")
      (fields (field (name "MPN") "RC0603FR-0710KL"))
      (libsource (lib "eagle-import") (part "SMD-RES-10K-1%-1/10W(0603)"))
    )
    (comp (ref "R46")
      (value "10K")
      (footprint "eagle-import:R0603")
      (fields (field (name "MPN") "RC0603FR-0710KL"))
      (libsource (lib "eagle-import") (part "SMD-RES-10K-1%-1/10W(0603)"))
    )
    (comp (ref "R47")
      (value "100K")
      (footprint "eagle-import:R0603")
      (fields (field (name "MPN") "RC0603FR-07100KL"))
      (libsource (lib "eagle-import") (part "SMD-RES-100K-1%-1/10W(0603)"))
    )
    (comp (ref "R48")
      (value "100K")
      (footprint "eagle-import:R0603")
      (fields (field (name "MPN") "RC0603FR-07100KL"))
      (libsource (lib "eagle-import") (part "SMD-RES-100K-1%-1/10W(0603)"))
    )
    (comp (ref "R49")
      (value "10K")
      (footprint "eagle-import:R0603")
      (fields (field (name "MPN") "RC0603FR-0710KL"))
      (libsource (lib "eagle-import") (part "SMD-RES-10K-1%-1/10W(0603)"))
    )
    (comp (ref "R50")
      (value "100K")
      (footprint "eagle-import:R0603")
      (fields (field (name "MPN") "RC0603FR-07100KL"))
      (libsource (lib "eagle-import") (part "SMD-RES-100K-1%-1/10W(0603)"))
    )
    (comp (ref "R51")
      (value "10K")
      (footprint "eagle-import:R0603")
      (fields (field (name "MPN") "RC0603FR-0710KL"))
      (libsource (lib "eagle-import") (part "SMD-RES-10K-1%-1/10W(0603)"))
    )
    (comp (ref "R52")
      (value "10K")
      (footprint "eagle-import:R0603")
      (fields (field (name "MPN") "RC0603FR-0710KL"))
      (libsource (lib "eagle-import") (part "SMD-RES-10K-1%-1/10W(0603)"))
    )
    (comp (ref "R53")
      (value "100K")
      (footprint "eagle-import:R0603")
      (fields (field (name "MPN") "RC0603FR-07100KL"))
      (libsource (lib "eagle-import") (part "SMD-RES-100K-1%-1/10W(0603)"))
    )
    (comp (ref "R54")
      (value "10R")
      (footprint "eagle-import:R0603")
      (fields (field (name "MPN") "RC0603FR-0710RL"))
      (libsource (lib "eagle-import") (part "SMD-RES-10R-1%-1/10W(0603)"))
    )
    (comp (ref "R55")
      (value "100K")
      (footprint "eagle-import:R0603")
      (fields (field (name "MPN") "RC0603FR-07100KL"))
      (libsource (lib "eagle-import") (part "SMD-RES-100K-1%-1/10W(0603)"))
    )
    (comp (ref "R56")
      (value "1K")
      (footprint "eagle-import:R0603")
      (fields (field (name "MPN") "RC0603FR-071KL"))
      (libsource (lib "eagle-import") (part "SMD-RES-1K-1%-1/10W(0603)"))
    )
    (comp (ref "S2")
      (value "DP03")
      (footprint "eagle-import:DP-03")
      (fields (field (name "MPN") "MCDP03"))
      (libsource (lib "eagle-import") (part "DP03"))
    )
    (comp (ref "S3")
      (value "DP03")
      (footprint "eagle-import:DP-03")
      (fields (field (name "MPN") "MCDP03"))
      (libsource (lib "eagle-import") (part "DP03"))
    )
    (comp (ref "S4")
      (value "DP03")
      (footprint "eagle-import:DP-03")
      (fields (field (name "MPN") "MCDP03"))
      (libsource (lib "eagle-import") (part "DP03"))
    )
    (comp (ref "S5")
      (value "DP03")
      (footprint "eagle-import:DP-03")
      (fields (field (name "MPN") "MCDP03"))
      (libsource (lib "eagle-import") (part "DP03"))
    )
    (comp (ref "S6")
      (value "DP03")
      (footprint "eagle-import:DP-03")
      (fields (field (name "MPN") "MCDP03"))
      (libsource (lib "eagle-import") (part "DP03"))
    )
    (comp (ref "S7")
      (value "DP03")
      (footprint "eagle-import:DP-03")
      (fields (field (name "MPN") "MCDP03"))
      (libsource (lib "eagle-import") (part "DP03"))
    )
    (comp (ref "S8")
      (value "DP03")
      (footprint "eagle-import:DP-03")
      (fields (field (name "MPN") "MCDP03"))
      (libsource (lib "eagle-import") (part "DP03"))
    )
    (comp (ref "S9")
      (value "DP03")
      (footprint "eagle-import:DP-03")
      (fields (field (name "MPN") "MCDP03"))
      (libsource (lib "eagle-import") (part "DP03"))
    )
    (comp (ref "S10")
      (value "DP03")
      (footprint "eagle-import:DP-03")
      (fields (field (name "MPN") "MCDP03"))
      (libsource (lib "eagle-import") (part "DP03"))
    )
    (comp (ref "SW1")
      (value "B3U-1000P-2P-SMD")
      (footprint "eagle-import:SW2-2.6-3.0X2.5X1.2+0.4MM")
      (libsource (lib "eagle-import") (part "SMD-BUTTON(2P-3.0X2.5X1.2+0.4MM)-B3U-1000P-2P-SMD"))
    )
    (comp (ref "THERM")
      (value "CONN_063.5MM-6")
      (footprint "eagle-import:SCREWTERMINAL-3.5MM-6")
      (libsource (lib "eagle-import") (part "CONN_063.5MM-6"))
    )
    (comp (ref "U$1")
      (value "A4988BREAKOUT")
      (footprint "eagle-import:A4988BREAKOUT")
      (libsource (lib "eagle-import") (part "A4988BREAKOUT"))
    )
    (comp (ref "U$2")
      (value "A4988BREAKOUT")
      (footprint "eagle-import:A4988BREAKOUT")
      (libsource (lib "eagle-import") (part "A4988BREAKOUT"))
    )
    (comp (ref "U$4")
      (value "A4988BREAKOUT")
      (footprint "eagle-import:A4988BREAKOUT")
      (libsource (lib "eagle-import") (part "A4988BREAKOUT"))
    )
    (comp (ref "U$5")
      (value "A4988BREAKOUT")
      (footprint "eagle-import:A4988BREAKOUT")
      (libsource (lib "eagle-import") (part "A4988BREAKOUT"))
    )
    (comp (ref "U$7")
      (value "A4988BREAKOUT")
      (footprint "eagle-import:A4988BREAKOUT")
      (libsource (lib "eagle-import") (part "A4988BREAKOUT"))
    )
    (comp (ref "U$8")
      (value "A4988BREAKOUT")
      (footprint "eagle-import:A4988BREAKOUT")
      (libsource (lib "eagle-import") (part "A4988BREAKOUT"))
    )
    (comp (ref "U$9")
      (value "A4988BREAKOUT")
      (footprint "eagle-import:A4988BREAKOUT")
      (libsource (lib "eagle-import") (part "A4988BREAKOUT"))
    )
    (comp (ref "U$10")
      (value "A4988BREAKOUT")
      (footprint "eagle-import:A4988BREAKOUT")
      (libsource (lib "eagle-import") (part "A4988BREAKOUT"))
    )
    (comp (ref "X")
      (value "A4988BREAKOUT")
      (footprint "eagle-import:A4988BREAKOUT")
      (libsource (lib "eagle-import") (part "A4988BREAKOUT"))
    )
    (comp (ref "X+")
      (value "PINHD-1X3")
      (footprint "eagle-import:1X03")
      (libsource (lib "eagle-import") (part "PINHD-1X3"))
    )
    (comp (ref "X-")
      (value "PINHD-1X3")
      (footprint "eagle-import:1X03")
      (libsource (lib "eagle-import") (part "PINHD-1X3"))
    )
    (comp (ref "X-MOT")
      (value "CONN_04SCREW_LOCK")
      (footprint "eagle-import:SCREWTERMINAL-3.5MM-4_LOCK")
      (libsource (lib "eagle-import") (part "CONN_04SCREW_LOCK"))
    )
    (comp (ref "Y+")
      (value "PINHD-1X3")
      (footprint "eagle-import:1X03")
      (libsource (lib "eagle-import") (part "PINHD-1X3"))
    )
    (comp (ref "Y-")
      (value "PINHD-1X3")
      (footprint "eagle-import:1X03")
      (libsource (lib "eagle-import") (part "PINHD-1X3"))
    )
    (comp (ref "Y-MOT")
      (value "CONN_04SCREW_LOCK")
      (footprint "eagle-import:SCREWTERMINAL-3.5MM-4_LOCK")
      (libsource (lib "eagle-import") (part "CONN_04SCREW_LOCK"))
    )
    (comp (ref "Y1")
      (value "16MHz")
      (footprint "eagle-import:HC49US")
      (libsource (lib "eagle-import") (part "CRYSTAL-16MHZPTH-HC49US"))
    )
    (comp (ref "Y2")
      (value "16MHz")
      (footprint "eagle-import:HC49US")
      (libsource (lib "eagle-import") (part "CRYSTAL-16MHZPTH-HC49US"))
    )
    (comp (ref "Z+")
      (value "PINHD-1X3")
      (footprint "eagle-import:1X03")
      (libsource (lib "eagle-import") (part "PINHD-1X3"))
    )
    (comp (ref "Z-")
      (value "PINHD-1X3")
      (footprint "eagle-import:1X03")
      (libsource (lib "eagle-import") (part "PINHD-1X3"))
    )
    (comp (ref "Z-MOT")
      (value "CONN_04SCREW_LOCK")
      (footprint "eagle-import:SCREWTERMINAL-3.5MM-4_LOCK")
      (libsource (lib "eagle-import") (part "CONN_04SCREW_LOCK"))
    )
    (comp (ref "Z-MOT1")
      (value "CONN_04SCREW_LOCK")
      (footprint "eagle-import:SCREWTERMINAL-3.5MM-4_LOCK")
      (libsource (lib "eagle-import") (part "CONN_04SCREW_LOCK"))
    )
  )
  (nets
    (net (code "1") (name "+12V") (class "Default")
      (node (ref "C10") (pin "+") (pinfunction "+_+") (pintype "passive"))
      (node (ref "C11") (pin "+") (pinfunction "+_+") (pintype "passive"))
      (node (ref "C12") (pin "+") (pinfunction "+_+") (pintype "passive"))
      (node (ref "C13") (pin "+") (pinfunction "+_+") (pintype "passive"))
      (node (ref "C14") (pin "+") (pinfunction "+_+") (pintype "passive"))
      (node (ref "C15") (pin "+") (pinfunction "+_+") (pintype "passive"))
      (node (ref "C25") (pin "-") (pinfunction "-_-") (pintype "passive"))
      (node (ref "C26") (pin "+") (pinfunction "+_+") (pintype "passive"))
      (node (ref "C7") (pin "+") (pinfunction "+_+") (pintype "passive"))
      (node (ref "C8") (pin "+") (pinfunction "+_+") (pintype "passive"))
      (node (ref "C9") (pin "+") (pinfunction "+_+") (pintype "passive"))
      (node (ref "L3") (pin "2") (pinfunction "2_2") (pintype "passive"))
      (node (ref "PWRF0") (pin "3") (pinfunction "3_3") (pintype "passive"))
      (node (ref "PWRF1") (pin "3") (pinfunction "3_3") (pintype "passive"))
      (node (ref "R42") (pin "2") (pinfunction "2_2") (pintype "passive"))
      (node (ref "U$1") (pin "VMOT") (pinfunction "VMOT_VMOT") (pintype "power_in"))
      (node (ref "U$10") (pin "VMOT") (pinfunction "VMOT_VMOT") (pintype "power_in"))
      (node (ref "U$2") (pin "VMOT") (pinfunction "VMOT_VMOT") (pintype "power_in"))
      (node (ref "U$4") (pin "VMOT") (pinfunction "VMOT_VMOT") (pintype "power_in"))
      (node (ref "U$5") (pin "VMOT") (pinfunction "VMOT_VMOT") (pintype "power_in"))
      (node (ref "U$7") (pin "VMOT") (pinfunction "VMOT_VMOT") (pintype "power_in"))
      (node (ref "U$8") (pin "VMOT") (pinfunction "VMOT_VMOT") (pintype "power_in"))
      (node (ref "U$9") (pin "VMOT") (pinfunction "VMOT_VMOT") (pintype "power_in"))
      (node (ref "X") (pin "VMOT") (pinfunction "VMOT_VMOT") (pintype "power_in"))
    )
    (net (code "2") (name "/2-1") (class "Default")
      (node (ref "AUX2") (pin "2") (pinfunction "2_2") (pintype "passive"))
      (node (ref "JP1") (pin "25") (pinfunction "25_25") (pintype "passive"))
    )
    (net (code "3") (name "/2-2") (class "Default")
      (node (ref "AUX2") (pin "6") (pinfunction "6_6") (pintype "passive"))
      (node (ref "JP1") (pin "23") (pinfunction "23_23") (pintype "passive"))
    )
    (net (code "4") (name "/CAPA") (class "Default")
      (node (ref "C22") (pin "+") (pinfunction "+_+") (pintype "passive"))
      (node (ref "JP4") (pin "24") (pinfunction "24_24") (pintype "passive"))
    )
    (net (code "5") (name "/D+") (class "Default")
      (node (ref "IC3") (pin "29") (pinfunction "D+_29") (pintype "bidirectional"))
      (node (ref "R11") (pin "2") (pinfunction "2_2") (pintype "passive"))
      (node (ref "R13") (pin "2") (pinfunction "2_2") (pintype "passive"))
    )
    (net (code "6") (name "/D-") (class "Default")
      (node (ref "IC3") (pin "30") (pinfunction "D-_30") (pintype "bidirectional"))
      (node (ref "R12") (pin "2") (pinfunction "2_2") (pintype "passive"))
      (node (ref "R14") (pin "2") (pinfunction "2_2") (pintype "passive"))
    )
    (net (code "7") (name "/DTR") (class "Default")
      (node (ref "C21") (pin "+") (pinfunction "+_+") (pintype "passive"))
      (node (ref "IC3") (pin "14") (pinfunction "PB0(SS/PCINT0)_14") (pintype "bidirectional"))
      (node (ref "R34") (pin "2") (pinfunction "2_2") (pintype "passive"))
    )
    (net (code "8") (name "/E0-DIR") (class "Default")
      (node (ref "JP2") (pin "9") (pinfunction "9_9") (pintype "passive"))
      (node (ref "U$1") (pin "DIR") (pinfunction "DIR_DIR") (pintype "input"))
    )
    (net (code "9") (name "/E0-EN") (class "Default")
      (node (ref "JP2") (pin "11") (pinfunction "11_11") (pintype "passive"))
      (node (ref "R8") (pin "1") (pinfunction "1_1") (pintype "passive"))
      (node (ref "U$1") (pin "EN") (pinfunction "EN_EN") (pintype "input"))
    )
    (net (code "10") (name "/E0-STEP") (class "Default")
      (node (ref "JP2") (pin "12") (pinfunction "12_12") (pintype "passive"))
      (node (ref "U$1") (pin "STEP") (pinfunction "STEP_STEP") (pintype "input"))
    )
    (net (code "11") (name "/E1-DIR") (class "Default")
      (node (ref "JP2") (pin "16") (pinfunction "16_16") (pintype "passive"))
      (node (ref "U$2") (pin "DIR") (pinfunction "DIR_DIR") (pintype "input"))
    )
    (net (code "12") (name "/E1-EN") (class "Default")
      (node (ref "JP2") (pin "13") (pinfunction "13_13") (pintype "passive"))
      (node (ref "R45") (pin "1") (pinfunction "1_1") (pintype "passive"))
      (node (ref "U$2") (pin "EN") (pinfunction "EN_EN") (pintype "input"))
    )
    (net (code "13") (name "/E1-STEP") (class "Default")
      (node (ref "JP2") (pin "15") (pinfunction "15_15") (pintype "passive"))
      (node (ref "U$2") (pin "STEP") (pinfunction "STEP_STEP") (pintype "input"))
    )
    (net (code "14") (name "/E2-DIR") (class "Default")
      (node (ref "JP3") (pin "26") (pinfunction "26_26") (pintype "passive"))
      (node (ref "U$7") (pin "DIR") (pinfunction "DIR_DIR") (pintype "input"))
    )
    (net (code "15") (name "/E2-EN") (class "Default")
      (node (ref "JP2") (pin "26") (pinfunction "26_26") (pintype "passive"))
      (node (ref "R10") (pin "1") (pinfunction "1_1") (pintype "passive"))
      (node (ref "U$7") (pin "EN") (pinfunction "EN_EN") (pintype "input"))
    )
    (net (code "16") (name "/E2-STEP") (class "Default")
      (node (ref "JP3") (pin "25") (pinfunction "25_25") (pintype "passive"))
      (node (ref "U$7") (pin "STEP") (pinfunction "STEP_STEP") (pintype "input"))
    )
    (net (code "17") (name "/E3-DIR") (class "Default")
      (node (ref "JP4") (pin "19") (pinfunction "19_19") (pintype "passive"))
      (node (ref "U$8") (pin "DIR") (pinfunction "DIR_DIR") (pintype "input"))
    )
    (net (code "18") (name "/E3-EN") (class "Default")
      (node (ref "JP4") (pin "21") (pinfunction "21_21") (pintype "passive"))
      (node (ref "R46") (pin "1") (pinfunction "1_1") (pintype "passive"))
      (node (ref "U$8") (pin "EN") (pinfunction "EN_EN") (pintype "input"))
    )
    (net (code "19") (name "/E3-STEP") (class "Default")
      (node (ref "JP4") (pin "22") (pinfunction "22_22") (pintype "passive"))
      (node (ref "U$8") (pin "STEP") (pinfunction "STEP_STEP") (pintype "input"))
    )
    (net (code "20") (name "/E4-DIR") (class "Default")
      (node (ref "JP4") (pin "13") (pinfunction "13_13") (pintype "passive"))
      (node (ref "U$9") (pin "DIR") (pinfunction "DIR_DIR") (pintype "input"))
    )
    (net (code "21") (name "/E4-EN") (class "Default")
      (node (ref "JP4") (pin "15") (pinfunction "15_15") (pintype "passive"))
      (node (ref "R33") (pin "1") (pinfunction "1_1") (pintype "passive"))
      (node (ref "U$9") (pin "EN") (pinfunction "EN_EN") (pintype "input"))
    )
    (net (code "22") (name "/E4-STEP") (class "Default")
      (node (ref "JP4") (pin "16") (pinfunction "16_16") (pintype "passive"))
      (node (ref "U$9") (pin "STEP") (pinfunction "STEP_STEP") (pintype "input"))
    )
    (net (code "23") (name "/E5-DIR") (class "Default")
      (node (ref "JP4") (pin "8") (pinfunction "8_8") (pintype "passive"))
      (node (ref "U$10") (pin "DIR") (pinfunction "DIR_DIR") (pintype "input"))
    )
    (net (code "24") (name "/E5-EN") (class "Default")
      (node (ref "JP4") (pin "10") (pinfunction "10_10") (pintype "passive"))
      (node (ref "R27") (pin "1") (pinfunction "1_1") (pintype "passive"))
      (node (ref "U$10") (pin "EN") (pinfunction "EN_EN") (pintype "input"))
    )
    (net (code "25") (name "/E5-STEP") (class "Default")
      (node (ref "JP4") (pin "7") (pinfunction "7_7") (pintype "passive"))
      (node (ref "U$10") (pin "STEP") (pinfunction "STEP_STEP") (pintype "input"))
    )
    (net (code "26") (name "/FAN0") (class "Default")
      (node (ref "JP3") (pin "5") (pinfunction "5_5") (pintype "passive"))
      (node (ref "R37") (pin "1") (pinfunction "1_1") (pintype "passive"))
      (node (ref "R38") (pin "1") (pinfunction "1_1") (pintype "passive"))
      (node (ref "R39") (pin "2") (pinfunction "2_2") (pintype "passive"))
    )
    (net (code "27") (name "/FAN1") (class "Default")
      (node (ref "JP3") (pin "6") (pinfunction "6_6") (pintype "passive"))
      (node (ref "R54") (pin "1") (pinfunction "1_1") (pintype "passive"))
      (node (ref "R55") (pin "1") (pinfunction "1_1") (pintype "passive"))
      (node (ref "R56") (pin "2") (pinfunction "2_2") (pintype "passive"))
    )
    (net (code "28") (name "/H0") (class "Default")
      (node (ref "JP1") (pin "18") (pinfunction "18_18") (pintype "passive"))
      (node (ref "R18") (pin "1") (pinfunction "1_1") (pintype "passive"))
      (node (ref "R19") (pin "1") (pinfunction "1_1") (pintype "passive"))
      (node (ref "R20") (pin "2") (pinfunction "2_2") (pintype "passive"))
    )
    (net (code "29") (name "/H1") (class "Default")
      (node (ref "JP1") (pin "17") (pinfunction "17_17") (pintype "passive"))
      (node (ref "R21") (pin "1") (pinfunction "1_1") (pintype "passive"))
      (node (ref "R22") (pin "1") (pinfunction "1_1") (pintype "passive"))
      (node (ref "R23") (pin "2") (pinfunction "2_2") (pintype "passive"))
    )
    (net (code "30") (name "/LED") (class "Default")
      (node (ref "JP2") (pin "2") (pinfunction "2_2") (pintype "passive"))
      (node (ref "R1") (pin "1") (pinfunction "1_1") (pintype "passive"))
    )
    (net (code "31") (name "/MISO") (class "Default")
      (node (ref "AUX2") (pin "3") (pinfunction "3_3") (pintype "passive"))
      (node (ref "JP1") (pin "22") (pinfunction "22_22") (pintype "passive"))
    )
    (net (code "32") (name "/MISO2") (class "Default")
      (node (ref "IC3") (pin "17") (pinfunction "PB3(PDO/MISO/PCINT3)_17") (pintype "bidirectional"))
      (node (ref "JP5") (pin "1") (pinfunction "1_1") (pintype "passive"))
    )
    (net (code "33") (name "/MOSI") (class "Default")
      (node (ref "AUX2") (pin "4") (pinfunction "4_4") (pintype "passive"))
      (node (ref "JP1") (pin "21") (pinfunction "21_21") (pintype "passive"))
    )
    (net (code "34") (name "/MOSI2") (class "Default")
      (node (ref "IC3") (pin "16") (pinfunction "PB2(PDI/MOSI/PCINT2)_16") (pintype "bidirectional"))
      (node (ref "JP5") (pin "4") (pinfunction "4_4") (pintype "passive"))
    )
    (net (code "35") (name "/PE0") (class "Default")
      (node (ref "AUX1") (pin "6") (pinfunction "6_6") (pintype "passive"))
      (node (ref "JP1") (pin "2") (pinfunction "2_2") (pintype "passive"))
      (node (ref "R28") (pin "1") (pinfunction "1_1") (pintype "passive"))
    )
    (net (code "36") (name "/PE1") (class "Default")
      (node (ref "AUX1") (pin "8") (pinfunction "8_8") (pintype "passive"))
      (node (ref "JP1") (pin "3") (pinfunction "3_3") (pintype "passive"))
      (node (ref "R29") (pin "1") (pinfunction "1_1") (pintype "passive"))
    )
    (net (code "37") (name "/PF4") (class "Default")
      (node (ref "AUX1") (pin "5") (pinfunction "5_5") (pintype "passive"))
      (node (ref "JP4") (pin "17") (pinfunction "17_17") (pintype "passive"))
    )
    (net (code "38") (name "/PF5") (class "Default")
      (node (ref "AUX1") (pin "7") (pinfunction "7_7") (pintype "passive"))
      (node (ref "JP4") (pin "18") (pinfunction "18_18") (pintype "passive"))
    )
    (net (code "39") (name "/RESET") (class "Default")
      (node (ref "C21") (pin "-") (pinfunction "-_-") (pintype "passive"))
      (node (ref "C27") (pin "1") (pinfunction "1_1") (pintype "passive"))
      (node (ref "D10") (pin "1") (pinfunction "+_1") (pintype "passive"))
      (node (ref "JP2") (pin "6") (pinfunction "6_6") (pintype "passive"))
      (node (ref "R36") (pin "1") (pinfunction "1_1") (pintype "passive"))
      (node (ref "SW1") (pin "2") (pinfunction "2_2") (pintype "bidirectional"))
    )
    (net (code "40") (name "/RESETU") (class "Default")
      (node (ref "D2") (pin "1") (pinfunction "+_1") (pintype "passive"))
      (node (ref "IC3") (pin "24") (pinfunction "/RESET(PC1)_24") (pintype "bidirectional"))
      (node (ref "JP5") (pin "5") (pinfunction "5_5") (pintype "passive"))
      (node (ref "R16") (pin "1") (pinfunction "1_1") (pintype "passive"))
    )
    (net (code "41") (name "/SCK") (class "Default")
      (node (ref "AUX2") (pin "5") (pinfunction "5_5") (pintype "passive"))
      (node (ref "JP1") (pin "20") (pinfunction "20_20") (pintype "passive"))
    )
    (net (code "42") (name "/SCK2") (class "Default")
      (node (ref "IC3") (pin "15") (pinfunction "PB1(SCK/PCINT1)_15") (pintype "bidirectional"))
      (node (ref "JP5") (pin "3") (pinfunction "3_3") (pintype "passive"))
    )
    (net (code "43") (name "/SCL") (class "Default")
      (node (ref "I2C") (pin "3") (pinfunction "3_3") (pintype "passive"))
      (node (ref "JP2") (pin "17") (pinfunction "17_17") (pintype "passive"))
      (node (ref "R6") (pin "1") (pinfunction "1_1") (pintype "passive"))
    )
    (net (code "44") (name "/SDA") (class "Default")
      (node (ref "I2C") (pin "4") (pinfunction "4_4") (pintype "passive"))
      (node (ref "JP2") (pin "20") (pinfunction "20_20") (pintype "passive"))
      (node (ref "R5") (pin "1") (pinfunction "1_1") (pintype "passive"))
    )
    (net (code "45") (name "/THERM0") (class "Default")
      (node (ref "C1") (pin "1") (pinfunction "1_1") (pintype "passive"))
      (node (ref "JP4") (pin "12") (pinfunction "12_12") (pintype "passive"))
      (node (ref "R2") (pin "1") (pinfunction "1_1") (pintype "passive"))
      (node (ref "THERM") (pin "2") (pinfunction "2_2") (pintype "passive"))
    )
    (net (code "46") (name "/THERM1") (class "Default")
      (node (ref "C2") (pin "1") (pinfunction "1_1") (pintype "passive"))
      (node (ref "JP4") (pin "9") (pinfunction "9_9") (pintype "passive"))
      (node (ref "R3") (pin "1") (pinfunction "1_1") (pintype "passive"))
      (node (ref "THERM") (pin "4") (pinfunction "4_4") (pintype "passive"))
    )
    (net (code "47") (name "/THERM2") (class "Default")
      (node (ref "C3") (pin "1") (pinfunction "1_1") (pintype "passive"))
      (node (ref "JP4") (pin "11") (pinfunction "11_11") (pintype "passive"))
      (node (ref "R4") (pin "1") (pinfunction "1_1") (pintype "passive"))
      (node (ref "THERM") (pin "6") (pinfunction "6_6") (pintype "passive"))
    )
    (net (code "48") (name "/USBVCC") (class "Default")
      (node (ref "C16") (pin "+") (pinfunction "+_+") (pintype "passive"))
      (node (ref "IC3") (pin "31") (pinfunction "UVCC_31") (pintype "bidirectional"))
      (node (ref "J1") (pin "VBUS") (pinfunction "VBUS_VBUS") (pintype "power_in"))
    )
    (net (code "49") (name "/X-DIR") (class "Default")
      (node (ref "JP3") (pin "4") (pinfunction "4_4") (pintype "passive"))
      (node (ref "X") (pin "DIR") (pinfunction "DIR_DIR") (pintype "input"))
    )
    (net (code "50") (name "/X-EN") (class "Default")
      (node (ref "JP3") (pin "1") (pinfunction "1_1") (pintype "passive"))
      (node (ref "R49") (pin "1") (pinfunction "1_1") (pintype "passive"))
      (node (ref "X") (pin "EN") (pinfunction "EN_EN") (pintype "input"))
    )
    (net (code "51") (name "/X-MAX") (class "Default")
      (node (ref "JP1") (pin "6") (pinfunction "6_6") (pintype "passive"))
      (node (ref "X+") (pin "1") (pinfunction "1_1") (pintype "passive"))
    )
    (net (code "52") (name "/X-MIN") (class "Default")
      (node (ref "JP1") (pin "5") (pinfunction "5_5") (pintype "passive"))
      (node (ref "X-") (pin "1") (pinfunction "1_1") (pintype "passive"))
    )
    (net (code "53") (name "/X-STEP") (class "Default")
      (node (ref "JP3") (pin "3") (pinfunction "3_3") (pintype "passive"))
      (node (ref "X") (pin "STEP") (pinfunction "STEP_STEP") (pintype "input"))
    )
    (net (code "54") (name "/XTAL1") (class "Default")
      (node (ref "C29") (pin "1") (pinfunction "1_1") (pintype "passive"))
      (node (ref "JP2") (pin "10") (pinfunction "10_10") (pintype "passive"))
      (node (ref "R17") (pin "1") (pinfunction "1_1") (pintype "passive"))
      (node (ref "Y1") (pin "1") (pinfunction "1_1") (pintype "passive"))
    )
    (net (code "55") (name "/XTAL2") (class "Default")
      (node (ref "C28") (pin "1") (pinfunction "1_1") (pintype "passive"))
      (node (ref "JP2") (pin "7") (pinfunction "7_7") (pintype "passive"))
      (node (ref "R17") (pin "2") (pinfunction "2_2") (pintype "passive"))
      (node (ref "Y1") (pin "2") (pinfunction "2_2") (pintype "passive"))
    )
    (net (code "56") (name "/XTALU1") (class "Default")
      (node (ref "C20") (pin "1") (pinfunction "1_1") (pintype "passive"))
      (node (ref "IC3") (pin "1") (pinfunction "XTAL1_1") (pintype "bidirectional"))
      (node (ref "R15") (pin "1") (pinfunction "1_1") (pintype "passive"))
      (node (ref "Y2") (pin "1") (pinfunction "1_1") (pintype "passive"))
    )
    (net (code "57") (name "/XTALU2") (class "Default")
      (node (ref "C19") (pin "1") (pinfunction "1_1") (pintype "passive"))
      (node (ref "IC3") (pin "2") (pinfunction "XTAL2/PC0_2") (pintype "bidirectional"))
      (node (ref "R15") (pin "2") (pinfunction "2_2") (pintype "passive"))
      (node (ref "Y2") (pin "2") (pinfunction "2_2") (pintype "passive"))
    )
    (net (code "58") (name "/Y-DIR") (class "Default")
      (node (ref "JP3") (pin "20") (pinfunction "20_20") (pintype "passive"))
      (node (ref "U$4") (pin "DIR") (pinfunction "DIR_DIR") (pintype "input"))
    )
    (net (code "59") (name "/Y-EN") (class "Default")
      (node (ref "JP3") (pin "17") (pinfunction "17_17") (pintype "passive"))
      (node (ref "R51") (pin "1") (pinfunction "1_1") (pintype "passive"))
      (node (ref "U$4") (pin "EN") (pinfunction "EN_EN") (pintype "input"))
    )
    (net (code "60") (name "/Y-MAX") (class "Default")
      (node (ref "JP1") (pin "7") (pinfunction "7_7") (pintype "passive"))
      (node (ref "Y+") (pin "1") (pinfunction "1_1") (pintype "passive"))
    )
    (net (code "61") (name "/Y-MIN") (class "Default")
      (node (ref "JP1") (pin "12") (pinfunction "12_12") (pintype "passive"))
      (node (ref "Y-") (pin "1") (pinfunction "1_1") (pintype "passive"))
    )
    (net (code "62") (name "/Y-STEP") (class "Default")
      (node (ref "JP3") (pin "18") (pinfunction "18_18") (pintype "passive"))
      (node (ref "U$4") (pin "STEP") (pinfunction "STEP_STEP") (pintype "input"))
    )
    (net (code "63") (name "/Z-DIR") (class "Default")
      (node (ref "JP3") (pin "24") (pinfunction "24_24") (pintype "passive"))
      (node (ref "U$5") (pin "DIR") (pinfunction "DIR_DIR") (pintype "input"))
    )
    (net (code "64") (name "/Z-EN") (class "Default")
      (node (ref "JP3") (pin "21") (pinfunction "21_21") (pintype "passive"))
      (node (ref "R52") (pin "1") (pinfunction "1_1") (pintype "passive"))
      (node (ref "U$5") (pin "EN") (pinfunction "EN_EN") (pintype "input"))
    )
    (net (code "65") (name "/Z-MAX") (class "Default")
      (node (ref "JP1") (pin "13") (pinfunction "13_13") (pintype "passive"))
      (node (ref "Z+") (pin "1") (pinfunction "1_1") (pintype "passive"))
    )
    (net (code "66") (name "/Z-MIN") (class "Default")
      (node (ref "JP1") (pin "15") (pinfunction "15_15") (pintype "passive"))
      (node (ref "Z-") (pin "1") (pinfunction "1_1") (pintype "passive"))
    )
    (net (code "67") (name "/Z-STEP") (class "Default")
      (node (ref "JP3") (pin "22") (pinfunction "22_22") (pintype "passive"))
      (node (ref "U$5") (pin "STEP") (pinfunction "STEP_STEP") (pintype "input"))
    )
    (net (code "68") (name "GND") (class "Default")
      (node (ref "AUX1") (pin "3") (pinfunction "3_3") (pintype "passive"))
      (node (ref "AUX1") (pin "4") (pinfunction "4_4") (pintype "passive"))
      (node (ref "AUX2") (pin "7") (pinfunction "7_7") (pintype "passive"))
      (node (ref "C1") (pin "2") (pinfunction "2_2") (pintype "passive"))
      (node (ref "C10") (pin "-") (pinfunction "-_-") (pintype "passive"))
      (node (ref "C11") (pin "-") (pinfunction "-_-") (pintype "passive"))
      (node (ref "C12") (pin "-") (pinfunction "-_-") (pintype "passive"))
      (node (ref "C13") (pin "-") (pinfunction "-_-") (pintype "passive"))
      (node (ref "C14") (pin "-") (pinfunction "-_-") (pintype "passive"))
      (node (ref "C15") (pin "-") (pinfunction "-_-") (pintype "passive"))
      (node (ref "C16") (pin "-") (pinfunction "-_-") (pintype "passive"))
      (node (ref "C17") (pin "-") (pinfunction "-_-") (pintype "passive"))
      (node (ref "C18") (pin "2") (pinfunction "2_2") (pintype "passive"))
      (node (ref "C19") (pin "2") (pinfunction "2_2") (pintype "passive"))
      (node (ref "C2") (pin "2") (pinfunction "2_2") (pintype "passive"))
      (node (ref "C20") (pin "2") (pinfunction "2_2") (pintype "passive"))
      (node (ref "C22") (pin "-") (pinfunction "-_-") (pintype "passive"))
      (node (ref "C23") (pin "-") (pinfunction "-_-") (pintype "passive"))
      (node (ref "C24") (pin "-") (pinfunction "-_-") (pintype "passive"))
      (node (ref "C26") (pin "-") (pinfunction "-_-") (pintype "passive"))
      (node (ref "C27") (pin "2") (pinfunction "2_2") (pintype "passive"))
      (node (ref "C28") (pin "2") (pinfunction "2_2") (pintype "passive"))
      (node (ref "C29") (pin "2") (pinfunction "2_2") (pintype "passive"))
      (node (ref "C3") (pin "2") (pinfunction "2_2") (pintype "passive"))
      (node (ref "C4") (pin "-") (pinfunction "-_-") (pintype "passive"))
      (node (ref "C6") (pin "-") (pinfunction "-_-") (pintype "passive"))
      (node (ref "C7") (pin "-") (pinfunction "-_-") (pintype "passive"))
      (node (ref "C8") (pin "-") (pinfunction "-_-") (pintype "passive"))
      (node (ref "C9") (pin "-") (pinfunction "-_-") (pintype "passive"))
      (node (ref "D11") (pin "-") (pinfunction "-_-") (pintype "passive"))
      (node (ref "D12") (pin "-") (pinfunction "-_-") (pintype "passive"))
      (node (ref "D14") (pin "-") (pinfunction "-_-") (pintype "passive"))
      (node (ref "D15") (pin "-") (pinfunction "-_-") (pintype "passive"))
      (node (ref "D3") (pin "A") (pinfunction "A_A") (pintype "passive"))
      (node (ref "D4") (pin "A") (pinfunction "A_A") (pintype "passive"))
      (node (ref "D5") (pin "1") (pinfunction "+_1") (pintype "passive"))
      (node (ref "D6") (pin "-") (pinfunction "-_-") (pintype "passive"))
      (node (ref "I2C") (pin "2") (pinfunction "2_2") (pintype "passive"))
      (node (ref "IC1") (pin "2") (pinfunction "GND_2") (pintype "power_in"))
      (node (ref "IC2") (pin "3") (pinfunction "GND_3") (pintype "power_in"))
      (node (ref "IC2") (pin "5") (pinfunction "EN_5") (pintype "input"))
      (node (ref "IC2") (pin "6") (pinfunction "GND_6") (pintype "power_in"))
      (node (ref "IC3") (pin "28") (pinfunction "UGND_28") (pintype "bidirectional"))
      (node (ref "IC3") (pin "3") (pinfunction "GND_3") (pintype "bidirectional"))
      (node (ref "J1") (pin "GND") (pinfunction "GND_GND") (pintype "power_in"))
      (node (ref "JP1") (pin "11") (pinfunction "11_11") (pintype "passive"))
      (node (ref "JP2") (pin "8") (pinfunction "8_8") (pintype "passive"))
      (node (ref "JP3") (pin "16") (pinfunction "16_16") (pintype "passive"))
      (node (ref "JP4") (pin "23") (pinfunction "23_23") (pintype "passive"))
      (node (ref "JP4") (pin "5") (pinfunction "5_5") (pintype "passive"))
      (node (ref "JP5") (pin "6") (pinfunction "6_6") (pintype "passive"))
      (node (ref "L1") (pin "2") (pinfunction "2_2") (pintype "passive"))
      (node (ref "MAIN-PWR") (pin "P1") (pinfunction "1_P1") (pintype "passive"))
      (node (ref "POWER") (pin "-") (pinfunction "-_-") (pintype "passive"))
      (node (ref "Q1") (pin "S") (pinfunction "S_S") (pintype "passive"))
      (node (ref "Q2") (pin "S") (pinfunction "S_S") (pintype "passive"))
      (node (ref "Q4") (pin "S") (pinfunction "S_S") (pintype "passive"))
      (node (ref "Q5") (pin "S") (pinfunction "S_S") (pintype "passive"))
      (node (ref "R18") (pin "2") (pinfunction "2_2") (pintype "passive"))
      (node (ref "R22") (pin "2") (pinfunction "2_2") (pintype "passive"))
      (node (ref "R24") (pin "1") (pinfunction "1_1") (pintype "passive"))
      (node (ref "R26") (pin "2") (pinfunction "2_2") (pintype "passive"))
      (node (ref "R32") (pin "2") (pinfunction "2_2") (pintype "passive"))
      (node (ref "R34") (pin "1") (pinfunction "1_1") (pintype "passive"))
      (node (ref "R38") (pin "2") (pinfunction "2_2") (pintype "passive"))
      (node (ref "R40") (pin "1") (pinfunction "1_1") (pintype "passive"))
      (node (ref "R44") (pin "2") (pinfunction "2_2") (pintype "passive"))
      (node (ref "R47") (pin "2") (pinfunction "2_2") (pintype "passive"))
      (node (ref "R48") (pin "2") (pinfunction "2_2") (pintype "passive"))
      (node (ref "R50") (pin "2") (pinfunction "2_2") (pintype "passive"))
      (node (ref "R53") (pin "2") (pinfunction "2_2") (pintype "passive"))
      (node (ref "R55") (pin "2") (pinfunction "2_2") (pintype "passive"))
      (node (ref "R7") (pin "2") (pinfunction "2_2") (pintype "passive"))
      (node (ref "R9") (pin "2") (pinfunction "2_2") (pintype "passive"))
      (node (ref "SW1") (pin "1") (pinfunction "1_1") (pintype "bidirectional"))
      (node (ref "THERM") (pin "1") (pinfunction "1_1") (pintype "passive"))
      (node (ref "THERM") (pin "3") (pinfunction "3_3") (pintype "passive"))
      (node (ref "THERM") (pin "5") (pinfunction "5_5") (pintype "passive"))
      (node (ref "U$1") (pin "GND") (pinfunction "GND_GND") (pintype "power_in"))
      (node (ref "U$1") (pin "GND@0") (pinfunction "GND_GND@0") (pintype "power_in"))
      (node (ref "U$10") (pin "GND") (pinfunction "GND_GND") (pintype "power_in"))
      (node (ref "U$10") (pin "GND@0") (pinfunction "GND_GND@0") (pintype "power_in"))
      (node (ref "U$2") (pin "GND") (pinfunction "GND_GND") (pintype "power_in"))
      (node (ref "U$2") (pin "GND@0") (pinfunction "GND_GND@0") (pintype "power_in"))
      (node (ref "U$4") (pin "GND") (pinfunction "GND_GND") (pintype "power_in"))
      (node (ref "U$4") (pin "GND@0") (pinfunction "GND_GND@0") (pintype "power_in"))
      (node (ref "U$5") (pin "GND") (pinfunction "GND_GND") (pintype "power_in"))
      (node (ref "U$5") (pin "GND@0") (pinfunction "GND_GND@0") (pintype "power_in"))
      (node (ref "U$7") (pin "GND") (pinfunction "GND_GND") (pintype "power_in"))
      (node (ref "U$7") (pin "GND@0") (pinfunction "GND_GND@0") (pintype "power_in"))
      (node (ref "U$8") (pin "GND") (pinfunction "GND_GND") (pintype "power_in"))
      (node (ref "U$8") (pin "GND@0") (pinfunction "GND_GND@0") (pintype "power_in"))
      (node (ref "U$9") (pin "GND") (pinfunction "GND_GND") (pintype "power_in"))
      (node (ref "U$9") (pin "GND@0") (pinfunction "GND_GND@0") (pintype "power_in"))
      (node (ref "X") (pin "GND") (pinfunction "GND_GND") (pintype "power_in"))
      (node (ref "X") (pin "GND@0") (pinfunction "GND_GND@0") (pintype "power_in"))
      (node (ref "X+") (pin "2") (pinfunction "2_2") (pintype "passive"))
      (node (ref "X-") (pin "2") (pinfunction "2_2") (pintype "passive"))
      (node (ref "Y+") (pin "2") (pinfunction "2_2") (pintype "passive"))
      (node (ref "Y-") (pin "2") (pinfunction "2_2") (pintype "passive"))
      (node (ref "Z+") (pin "2") (pinfunction "2_2") (pintype "passive"))
      (node (ref "Z-") (pin "2") (pinfunction "2_2") (pintype "passive"))
    )
    (net (code "69") (name "Net-(D1-+)") (class "Default")
      (node (ref "C5") (pin "+") (pinfunction "+_+") (pintype "passive"))
      (node (ref "D1") (pin "1") (pinfunction "+_1") (pintype "passive"))
      (node (ref "IC1") (pin "1") (pinfunction "BOOST_1") (pintype "passive"))
    )
    (net (code "70") (name "Net-(D6-Pad+)") (class "Default")
      (node (ref "D6") (pin "+") (pinfunction "+_+") (pintype "passive"))
      (node (ref "R1") (pin "2") (pinfunction "2_2") (pintype "passive"))
    )
    (net (code "71") (name "Net-(D7--)") (class "Default")
      (node (ref "C23") (pin "+") (pinfunction "+_+") (pintype "passive"))
      (node (ref "C24") (pin "+") (pinfunction "+_+") (pintype "passive"))
      (node (ref "D7") (pin "2") (pinfunction "-_2") (pintype "passive"))
      (node (ref "IC1") (pin "4") (pinfunction "#SHDN_4") (pintype "passive"))
      (node (ref "IC1") (pin "5") (pinfunction "V_IN_5") (pintype "passive"))
    )
    (net (code "72") (name "Net-(D8-Pad-)") (class "Default")
      (node (ref "D8") (pin "-") (pinfunction "-_-") (pintype "passive"))
      (node (ref "R31") (pin "2") (pinfunction "2_2") (pintype "passive"))
    )
    (net (code "73") (name "Net-(D9-Pad-)") (class "Default")
      (node (ref "D9") (pin "-") (pinfunction "-_-") (pintype "passive"))
      (node (ref "R30") (pin "2") (pinfunction "2_2") (pintype "passive"))
    )
    (net (code "74") (name "Net-(D11-Pad+)") (class "Default")
      (node (ref "D11") (pin "+") (pinfunction "+_+") (pintype "passive"))
      (node (ref "R20") (pin "1") (pinfunction "1_1") (pintype "passive"))
    )
    (net (code "75") (name "Net-(D12-Pad+)") (class "Default")
      (node (ref "D12") (pin "+") (pinfunction "+_+") (pintype "passive"))
      (node (ref "R23") (pin "1") (pinfunction "1_1") (pintype "passive"))
    )
    (net (code "76") (name "Net-(D14-Pad+)") (class "Default")
      (node (ref "D14") (pin "+") (pinfunction "+_+") (pintype "passive"))
      (node (ref "R39") (pin "1") (pinfunction "1_1") (pintype "passive"))
    )
    (net (code "77") (name "Net-(D15-Pad+)") (class "Default")
      (node (ref "D15") (pin "+") (pinfunction "+_+") (pintype "passive"))
      (node (ref "R56") (pin "1") (pinfunction "1_1") (pintype "passive"))
    )
    (net (code "78") (name "Net-(E0-MOT-Pad1)") (class "Default")
      (node (ref "E0-MOT") (pin "1") (pinfunction "1_1") (pintype "passive"))
      (node (ref "U$1") (pin "2B") (pinfunction "2B_2B") (pintype "output"))
    )
    (net (code "79") (name "Net-(E0-MOT-Pad2)") (class "Default")
      (node (ref "E0-MOT") (pin "2") (pinfunction "2_2") (pintype "passive"))
      (node (ref "U$1") (pin "2A") (pinfunction "2A_2A") (pintype "output"))
    )
    (net (code "80") (name "Net-(E0-MOT-Pad3)") (class "Default")
      (node (ref "E0-MOT") (pin "3") (pinfunction "3_3") (pintype "passive"))
      (node (ref "U$1") (pin "1A") (pinfunction "1A_1A") (pintype "output"))
    )
    (net (code "81") (name "Net-(E0-MOT-Pad4)") (class "Default")
      (node (ref "E0-MOT") (pin "4") (pinfunction "4_4") (pintype "passive"))
      (node (ref "U$1") (pin "1B") (pinfunction "1B_1B") (pintype "output"))
    )
    (net (code "82") (name "Net-(E1-MOT-Pad1)") (class "Default")
      (node (ref "E1-MOT") (pin "1") (pinfunction "1_1") (pintype "passive"))
      (node (ref "U$2") (pin "2B") (pinfunction "2B_2B") (pintype "output"))
    )
    (net (code "83") (name "Net-(E1-MOT-Pad2)") (class "Default")
      (node (ref "E1-MOT") (pin "2") (pinfunction "2_2") (pintype "passive"))
      (node (ref "U$2") (pin "2A") (pinfunction "2A_2A") (pintype "output"))
    )
    (net (code "84") (name "Net-(E1-MOT-Pad3)") (class "Default")
      (node (ref "E1-MOT") (pin "3") (pinfunction "3_3") (pintype "passive"))
      (node (ref "U$2") (pin "1A") (pinfunction "1A_1A") (pintype "output"))
    )
    (net (code "85") (name "Net-(E1-MOT-Pad4)") (class "Default")
      (node (ref "E1-MOT") (pin "4") (pinfunction "4_4") (pintype "passive"))
      (node (ref "U$2") (pin "1B") (pinfunction "1B_1B") (pintype "output"))
    )
    (net (code "86") (name "Net-(E2-MOT-Pad1)") (class "Default")
      (node (ref "E2-MOT") (pin "1") (pinfunction "1_1") (pintype "passive"))
      (node (ref "U$7") (pin "2B") (pinfunction "2B_2B") (pintype "output"))
    )
    (net (code "87") (name "Net-(E2-MOT-Pad2)") (class "Default")
      (node (ref "E2-MOT") (pin "2") (pinfunction "2_2") (pintype "passive"))
      (node (ref "U$7") (pin "2A") (pinfunction "2A_2A") (pintype "output"))
    )
    (net (code "88") (name "Net-(E2-MOT-Pad3)") (class "Default")
      (node (ref "E2-MOT") (pin "3") (pinfunction "3_3") (pintype "passive"))
      (node (ref "U$7") (pin "1A") (pinfunction "1A_1A") (pintype "output"))
    )
    (net (code "89") (name "Net-(E2-MOT-Pad4)") (class "Default")
      (node (ref "E2-MOT") (pin "4") (pinfunction "4_4") (pintype "passive"))
      (node (ref "U$7") (pin "1B") (pinfunction "1B_1B") (pintype "output"))
    )
    (net (code "90") (name "Net-(E3-MOT-Pad1)") (class "Default")
      (node (ref "E3-MOT") (pin "1") (pinfunction "1_1") (pintype "passive"))
      (node (ref "U$8") (pin "2B") (pinfunction "2B_2B") (pintype "output"))
    )
    (net (code "91") (name "Net-(E3-MOT-Pad2)") (class "Default")
      (node (ref "E3-MOT") (pin "2") (pinfunction "2_2") (pintype "passive"))
      (node (ref "U$8") (pin "2A") (pinfunction "2A_2A") (pintype "output"))
    )
    (net (code "92") (name "Net-(E3-MOT-Pad3)") (class "Default")
      (node (ref "E3-MOT") (pin "3") (pinfunction "3_3") (pintype "passive"))
      (node (ref "U$8") (pin "1A") (pinfunction "1A_1A") (pintype "output"))
    )
    (net (code "93") (name "Net-(E3-MOT-Pad4)") (class "Default")
      (node (ref "E3-MOT") (pin "4") (pinfunction "4_4") (pintype "passive"))
      (node (ref "U$8") (pin "1B") (pinfunction "1B_1B") (pintype "output"))
    )
    (net (code "94") (name "Net-(E4-MOT-Pad1)") (class "Default")
      (node (ref "E4-MOT") (pin "1") (pinfunction "1_1") (pintype "passive"))
      (node (ref "U$9") (pin "2B") (pinfunction "2B_2B") (pintype "output"))
    )
    (net (code "95") (name "Net-(E4-MOT-Pad2)") (class "Default")
      (node (ref "E4-MOT") (pin "2") (pinfunction "2_2") (pintype "passive"))
      (node (ref "U$9") (pin "2A") (pinfunction "2A_2A") (pintype "output"))
    )
    (net (code "96") (name "Net-(E4-MOT-Pad3)") (class "Default")
      (node (ref "E4-MOT") (pin "3") (pinfunction "3_3") (pintype "passive"))
      (node (ref "U$9") (pin "1A") (pinfunction "1A_1A") (pintype "output"))
    )
    (net (code "97") (name "Net-(E4-MOT-Pad4)") (class "Default")
      (node (ref "E4-MOT") (pin "4") (pinfunction "4_4") (pintype "passive"))
      (node (ref "U$9") (pin "1B") (pinfunction "1B_1B") (pintype "output"))
    )
    (net (code "98") (name "Net-(E5-MOT-Pad1)") (class "Default")
      (node (ref "E5-MOT") (pin "1") (pinfunction "1_1") (pintype "passive"))
      (node (ref "U$10") (pin "2B") (pinfunction "2B_2B") (pintype "output"))
    )
    (net (code "99") (name "Net-(E5-MOT-Pad2)") (class "Default")
      (node (ref "E5-MOT") (pin "2") (pinfunction "2_2") (pintype "passive"))
      (node (ref "U$10") (pin "2A") (pinfunction "2A_2A") (pintype "output"))
    )
    (net (code "100") (name "Net-(E5-MOT-Pad3)") (class "Default")
      (node (ref "E5-MOT") (pin "3") (pinfunction "3_3") (pintype "passive"))
      (node (ref "U$10") (pin "1A") (pinfunction "1A_1A") (pintype "output"))
    )
    (net (code "101") (name "Net-(E5-MOT-Pad4)") (class "Default")
      (node (ref "E5-MOT") (pin "4") (pinfunction "4_4") (pintype "passive"))
      (node (ref "U$10") (pin "1B") (pinfunction "1B_1B") (pintype "output"))
    )
    (net (code "102") (name "Net-(FAN0_1-Pad1)") (class "Default")
      (node (ref "FAN0_1") (pin "1") (pinfunction "1_1") (pintype "passive"))
      (node (ref "PWRF0") (pin "2") (pinfunction "2_2") (pintype "passive"))
    )
    (net (code "103") (name "Net-(FAN0_1-Pad2)") (class "Default")
      (node (ref "FAN0_1") (pin "2") (pinfunction "2_2") (pintype "passive"))
      (node (ref "Q4") (pin "D") (pinfunction "D_D") (pintype "passive"))
    )
    (net (code "104") (name "Net-(FAN1_1-Pad1)") (class "Default")
      (node (ref "FAN1_1") (pin "1") (pinfunction "1_1") (pintype "passive"))
      (node (ref "PWRF1") (pin "2") (pinfunction "2_2") (pintype "passive"))
    )
    (net (code "105") (name "Net-(FAN1_1-Pad2)") (class "Default")
      (node (ref "FAN1_1") (pin "2") (pinfunction "2_2") (pintype "passive"))
      (node (ref "Q5") (pin "D") (pinfunction "D_D") (pintype "passive"))
    )
    (net (code "106") (name "Net-(HE0-1)") (class "Default")
      (node (ref "HE0") (pin "P1") (pinfunction "1_P1") (pintype "passive"))
      (node (ref "Q1") (pin "D") (pinfunction "D_D") (pintype "passive"))
    )
    (net (code "107") (name "Net-(HE1-1)") (class "Default")
      (node (ref "HE1") (pin "P1") (pinfunction "1_P1") (pintype "passive"))
      (node (ref "Q2") (pin "D") (pinfunction "D_D") (pintype "passive"))
    )
    (net (code "108") (name "Net-(IC1-FB)") (class "Default")
      (node (ref "IC1") (pin "3") (pinfunction "FB_3") (pintype "passive"))
      (node (ref "R24") (pin "2") (pinfunction "2_2") (pintype "passive"))
      (node (ref "R43") (pin "1") (pinfunction "1_1") (pintype "passive"))
    )
    (net (code "109") (name "Net-(IC1-SW)") (class "Default")
      (node (ref "C5") (pin "-") (pinfunction "-_-") (pintype "passive"))
      (node (ref "D3") (pin "C") (pinfunction "C_C") (pintype "passive"))
      (node (ref "IC1") (pin "6") (pinfunction "SW_6") (pintype "passive"))
      (node (ref "L4") (pin "1") (pinfunction "1_1") (pintype "passive"))
    )
    (net (code "110") (name "Net-(IC2-FB)") (class "Default")
      (node (ref "C25") (pin "+") (pinfunction "+_+") (pintype "passive"))
      (node (ref "IC2") (pin "4") (pinfunction "FB_4") (pintype "input"))
      (node (ref "R40") (pin "2") (pinfunction "2_2") (pintype "passive"))
      (node (ref "R42") (pin "1") (pinfunction "1_1") (pintype "passive"))
    )
    (net (code "111") (name "Net-(IC2-OUT)") (class "Default")
      (node (ref "D4") (pin "C") (pinfunction "C_C") (pintype "passive"))
      (node (ref "IC2") (pin "2") (pinfunction "OUT_2") (pintype "output"))
      (node (ref "L3") (pin "1") (pinfunction "1_1") (pintype "passive"))
    )
    (net (code "112") (name "Net-(IC3-PD2(INT2{slash}AIN1{slash}RXD1))") (class "Default")
      (node (ref "IC3") (pin "8") (pinfunction "PD2(INT2/AIN1/RXD1)_8") (pintype "bidirectional"))
      (node (ref "R29") (pin "2") (pinfunction "2_2") (pintype "passive"))
    )
    (net (code "113") (name "Net-(IC3-PD3(INT3{slash}TXD1))") (class "Default")
      (node (ref "IC3") (pin "9") (pinfunction "PD3(INT3/TXD1)_9") (pintype "bidirectional"))
      (node (ref "R28") (pin "2") (pinfunction "2_2") (pintype "passive"))
    )
    (net (code "114") (name "Net-(IC3-PD4(INT5{slash}AIN3))") (class "Default")
      (node (ref "D9") (pin "+") (pinfunction "+_+") (pintype "passive"))
      (node (ref "IC3") (pin "10") (pinfunction "PD4(INT5/AIN3)_10") (pintype "bidirectional"))
    )
    (net (code "115") (name "Net-(IC3-PD5(XCK{slash}AIN4{slash}PCINT12))") (class "Default")
      (node (ref "D8") (pin "+") (pinfunction "+_+") (pintype "passive"))
      (node (ref "IC3") (pin "11") (pinfunction "PD5(XCK/AIN4/PCINT12)_11") (pintype "bidirectional"))
    )
    (net (code "116") (name "Net-(IC3-UCAP)") (class "Default")
      (node (ref "C18") (pin "1") (pinfunction "1_1") (pintype "passive"))
      (node (ref "IC3") (pin "27") (pinfunction "UCAP_27") (pintype "bidirectional"))
    )
    (net (code "117") (name "Net-(J1-PadD+)") (class "Default")
      (node (ref "J1") (pin "D+") (pinfunction "D+_D+") (pintype "bidirectional"))
      (node (ref "R11") (pin "1") (pinfunction "1_1") (pintype "passive"))
    )
    (net (code "118") (name "Net-(J1-PadD-)") (class "Default")
      (node (ref "J1") (pin "D-") (pinfunction "D-_D-") (pintype "bidirectional"))
      (node (ref "R12") (pin "1") (pinfunction "1_1") (pintype "passive"))
    )
    (net (code "119") (name "Net-(J1-SHIELD-PadSHLD1)") (class "Default")
      (node (ref "J1") (pin "SHLD1") (pinfunction "SHIELD_SHLD1") (pintype "bidirectional"))
      (node (ref "J1") (pin "SHLD2") (pinfunction "SHIELD_SHLD2") (pintype "bidirectional"))
      (node (ref "L1") (pin "1") (pinfunction "1_1") (pintype "passive"))
      (node (ref "R13") (pin "1") (pinfunction "1_1") (pintype "passive"))
      (node (ref "R14") (pin "1") (pinfunction "1_1") (pintype "passive"))
    )
    (net (code "120") (name "Net-(MAIN-PWR-2)") (class "Default")
      (node (ref "F1") (pin "1") (pinfunction "1_1") (pintype "passive"))
      (node (ref "MAIN-PWR") (pin "P2") (pinfunction "2_P2") (pintype "passive"))
    )
    (net (code "121") (name "Net-(Q1-PadG)") (class "Default")
      (node (ref "Q1") (pin "G") (pinfunction "G_G") (pintype "passive"))
      (node (ref "R19") (pin "2") (pinfunction "2_2") (pintype "passive"))
    )
    (net (code "122") (name "Net-(Q2-PadG)") (class "Default")
      (node (ref "Q2") (pin "G") (pinfunction "G_G") (pintype "passive"))
      (node (ref "R21") (pin "2") (pinfunction "2_2") (pintype "passive"))
    )
    (net (code "123") (name "Net-(Q4-PadG)") (class "Default")
      (node (ref "Q4") (pin "G") (pinfunction "G_G") (pintype "passive"))
      (node (ref "R37") (pin "2") (pinfunction "2_2") (pintype "passive"))
    )
    (net (code "124") (name "Net-(Q5-PadG)") (class "Default")
      (node (ref "Q5") (pin "G") (pinfunction "G_G") (pintype "passive"))
      (node (ref "R54") (pin "2") (pinfunction "2_2") (pintype "passive"))
    )
    (net (code "125") (name "Net-(R7-Pad1)") (class "Default")
      (node (ref "R7") (pin "1") (pinfunction "1_1") (pintype "passive"))
      (node (ref "S7") (pin "3") (pinfunction "3_3") (pintype "passive"))
      (node (ref "U$1") (pin "MS1") (pinfunction "MS1_MS1") (pintype "input"))
    )
    (net (code "126") (name "Net-(R9-Pad1)") (class "Default")
      (node (ref "R9") (pin "1") (pinfunction "1_1") (pintype "passive"))
      (node (ref "S10") (pin "3") (pinfunction "3_3") (pintype "passive"))
      (node (ref "U$7") (pin "MS1") (pinfunction "MS1_MS1") (pintype "input"))
    )
    (net (code "127") (name "Net-(R26-Pad1)") (class "Default")
      (node (ref "R26") (pin "1") (pinfunction "1_1") (pintype "passive"))
      (node (ref "S6") (pin "3") (pinfunction "3_3") (pintype "passive"))
      (node (ref "U$10") (pin "MS1") (pinfunction "MS1_MS1") (pintype "input"))
    )
    (net (code "128") (name "Net-(R32-Pad1)") (class "Default")
      (node (ref "R32") (pin "1") (pinfunction "1_1") (pintype "passive"))
      (node (ref "S9") (pin "3") (pinfunction "3_3") (pintype "passive"))
      (node (ref "U$9") (pin "MS1") (pinfunction "MS1_MS1") (pintype "input"))
    )
    (net (code "129") (name "Net-(R44-Pad1)") (class "Default")
      (node (ref "R44") (pin "1") (pinfunction "1_1") (pintype "passive"))
      (node (ref "S8") (pin "3") (pinfunction "3_3") (pintype "passive"))
      (node (ref "U$2") (pin "MS1") (pinfunction "MS1_MS1") (pintype "input"))
    )
    (net (code "130") (name "Net-(R47-Pad1)") (class "Default")
      (node (ref "R47") (pin "1") (pinfunction "1_1") (pintype "passive"))
      (node (ref "S5") (pin "3") (pinfunction "3_3") (pintype "passive"))
      (node (ref "U$8") (pin "MS1") (pinfunction "MS1_MS1") (pintype "input"))
    )
    (net (code "131") (name "Net-(R48-Pad1)") (class "Default")
      (node (ref "R48") (pin "1") (pinfunction "1_1") (pintype "passive"))
      (node (ref "S4") (pin "3") (pinfunction "3_3") (pintype "passive"))
      (node (ref "X") (pin "MS1") (pinfunction "MS1_MS1") (pintype "input"))
    )
    (net (code "132") (name "Net-(R50-Pad1)") (class "Default")
      (node (ref "R50") (pin "1") (pinfunction "1_1") (pintype "passive"))
      (node (ref "S3") (pin "3") (pinfunction "3_3") (pintype "passive"))
      (node (ref "U$4") (pin "MS1") (pinfunction "MS1_MS1") (pintype "input"))
    )
    (net (code "133") (name "Net-(R53-Pad1)") (class "Default")
      (node (ref "R53") (pin "1") (pinfunction "1_1") (pintype "passive"))
      (node (ref "S2") (pin "3") (pinfunction "3_3") (pintype "passive"))
      (node (ref "U$5") (pin "MS1") (pinfunction "MS1_MS1") (pintype "input"))
    )
    (net (code "134") (name "Net-(S2-Pad1)") (class "Default")
      (node (ref "S2") (pin "1") (pinfunction "1_1") (pintype "passive"))
      (node (ref "U$5") (pin "MS3") (pinfunction "MS3_MS3") (pintype "input"))
    )
    (net (code "135") (name "Net-(S2-Pad2)") (class "Default")
      (node (ref "S2") (pin "2") (pinfunction "2_2") (pintype "passive"))
      (node (ref "U$5") (pin "MS2") (pinfunction "MS2_MS2") (pintype "input"))
    )
    (net (code "136") (name "Net-(S3-Pad1)") (class "Default")
      (node (ref "S3") (pin "1") (pinfunction "1_1") (pintype "passive"))
      (node (ref "U$4") (pin "MS3") (pinfunction "MS3_MS3") (pintype "input"))
    )
    (net (code "137") (name "Net-(S3-Pad2)") (class "Default")
      (node (ref "S3") (pin "2") (pinfunction "2_2") (pintype "passive"))
      (node (ref "U$4") (pin "MS2") (pinfunction "MS2_MS2") (pintype "input"))
    )
    (net (code "138") (name "Net-(S4-Pad1)") (class "Default")
      (node (ref "S4") (pin "1") (pinfunction "1_1") (pintype "passive"))
      (node (ref "X") (pin "MS3") (pinfunction "MS3_MS3") (pintype "input"))
    )
    (net (code "139") (name "Net-(S4-Pad2)") (class "Default")
      (node (ref "S4") (pin "2") (pinfunction "2_2") (pintype "passive"))
      (node (ref "X") (pin "MS2") (pinfunction "MS2_MS2") (pintype "input"))
    )
    (net (code "140") (name "Net-(S5-Pad1)") (class "Default")
      (node (ref "S5") (pin "1") (pinfunction "1_1") (pintype "passive"))
      (node (ref "U$8") (pin "MS3") (pinfunction "MS3_MS3") (pintype "input"))
    )
    (net (code "141") (name "Net-(S5-Pad2)") (class "Default")
      (node (ref "S5") (pin "2") (pinfunction "2_2") (pintype "passive"))
      (node (ref "U$8") (pin "MS2") (pinfunction "MS2_MS2") (pintype "input"))
    )
    (net (code "142") (name "Net-(S6-Pad1)") (class "Default")
      (node (ref "S6") (pin "1") (pinfunction "1_1") (pintype "passive"))
      (node (ref "U$10") (pin "MS3") (pinfunction "MS3_MS3") (pintype "input"))
    )
    (net (code "143") (name "Net-(S6-Pad2)") (class "Default")
      (node (ref "S6") (pin "2") (pinfunction "2_2") (pintype "passive"))
      (node (ref "U$10") (pin "MS2") (pinfunction "MS2_MS2") (pintype "input"))
    )
    (net (code "144") (name "Net-(S7-Pad1)") (class "Default")
      (node (ref "S7") (pin "1") (pinfunction "1_1") (pintype "passive"))
      (node (ref "U$1") (pin "MS3") (pinfunction "MS3_MS3") (pintype "input"))
    )
    (net (code "145") (name "Net-(S7-Pad2)") (class "Default")
      (node (ref "S7") (pin "2") (pinfunction "2_2") (pintype "passive"))
      (node (ref "U$1") (pin "MS2") (pinfunction "MS2_MS2") (pintype "input"))
    )
    (net (code "146") (name "Net-(S8-Pad1)") (class "Default")
      (node (ref "S8") (pin "1") (pinfunction "1_1") (pintype "passive"))
      (node (ref "U$2") (pin "MS3") (pinfunction "MS3_MS3") (pintype "input"))
    )
    (net (code "147") (name "Net-(S8-Pad2)") (class "Default")
      (node (ref "S8") (pin "2") (pinfunction "2_2") (pintype "passive"))
      (node (ref "U$2") (pin "MS2") (pinfunction "MS2_MS2") (pintype "input"))
    )
    (net (code "148") (name "Net-(S9-Pad1)") (class "Default")
      (node (ref "S9") (pin "1") (pinfunction "1_1") (pintype "passive"))
      (node (ref "U$9") (pin "MS3") (pinfunction "MS3_MS3") (pintype "input"))
    )
    (net (code "149") (name "Net-(S9-Pad2)") (class "Default")
      (node (ref "S9") (pin "2") (pinfunction "2_2") (pintype "passive"))
      (node (ref "U$9") (pin "MS2") (pinfunction "MS2_MS2") (pintype "input"))
    )
    (net (code "150") (name "Net-(S10-Pad1)") (class "Default")
      (node (ref "S10") (pin "1") (pinfunction "1_1") (pintype "passive"))
      (node (ref "U$7") (pin "MS3") (pinfunction "MS3_MS3") (pintype "input"))
    )
    (net (code "151") (name "Net-(S10-Pad2)") (class "Default")
      (node (ref "S10") (pin "2") (pinfunction "2_2") (pintype "passive"))
      (node (ref "U$7") (pin "MS2") (pinfunction "MS2_MS2") (pintype "input"))
    )
    (net (code "152") (name "Net-(U$1-SLEEP)") (class "Default")
      (node (ref "U$1") (pin "RST") (pinfunction "RST_RST") (pintype "input"))
      (node (ref "U$1") (pin "SLP") (pinfunction "SLEEP_SLP") (pintype "input"))
    )
    (net (code "153") (name "Net-(U$2-SLEEP)") (class "Default")
      (node (ref "U$2") (pin "RST") (pinfunction "RST_RST") (pintype "input"))
      (node (ref "U$2") (pin "SLP") (pinfunction "SLEEP_SLP") (pintype "input"))
    )
    (net (code "154") (name "Net-(U$4-Pad1A)") (class "Default")
      (node (ref "U$4") (pin "1A") (pinfunction "1A_1A") (pintype "output"))
      (node (ref "Y-MOT") (pin "3") (pinfunction "3_3") (pintype "passive"))
    )
    (net (code "155") (name "Net-(U$4-Pad1B)") (class "Default")
      (node (ref "U$4") (pin "1B") (pinfunction "1B_1B") (pintype "output"))
      (node (ref "Y-MOT") (pin "4") (pinfunction "4_4") (pintype "passive"))
    )
    (net (code "156") (name "Net-(U$4-Pad2A)") (class "Default")
      (node (ref "U$4") (pin "2A") (pinfunction "2A_2A") (pintype "output"))
      (node (ref "Y-MOT") (pin "2") (pinfunction "2_2") (pintype "passive"))
    )
    (net (code "157") (name "Net-(U$4-Pad2B)") (class "Default")
      (node (ref "U$4") (pin "2B") (pinfunction "2B_2B") (pintype "output"))
      (node (ref "Y-MOT") (pin "1") (pinfunction "1_1") (pintype "passive"))
    )
    (net (code "158") (name "Net-(U$4-SLEEP)") (class "Default")
      (node (ref "U$4") (pin "RST") (pinfunction "RST_RST") (pintype "input"))
      (node (ref "U$4") (pin "SLP") (pinfunction "SLEEP_SLP") (pintype "input"))
    )
    (net (code "159") (name "Net-(U$5-Pad1A)") (class "Default")
      (node (ref "U$5") (pin "1A") (pinfunction "1A_1A") (pintype "output"))
      (node (ref "Z-MOT") (pin "3") (pinfunction "3_3") (pintype "passive"))
      (node (ref "Z-MOT1") (pin "3") (pinfunction "3_3") (pintype "passive"))
    )
    (net (code "160") (name "Net-(U$5-Pad1B)") (class "Default")
      (node (ref "U$5") (pin "1B") (pinfunction "1B_1B") (pintype "output"))
      (node (ref "Z-MOT") (pin "4") (pinfunction "4_4") (pintype "passive"))
      (node (ref "Z-MOT1") (pin "4") (pinfunction "4_4") (pintype "passive"))
    )
    (net (code "161") (name "Net-(U$5-Pad2A)") (class "Default")
      (node (ref "U$5") (pin "2A") (pinfunction "2A_2A") (pintype "output"))
      (node (ref "Z-MOT") (pin "2") (pinfunction "2_2") (pintype "passive"))
      (node (ref "Z-MOT1") (pin "2") (pinfunction "2_2") (pintype "passive"))
    )
    (net (code "162") (name "Net-(U$5-Pad2B)") (class "Default")
      (node (ref "U$5") (pin "2B") (pinfunction "2B_2B") (pintype "output"))
      (node (ref "Z-MOT") (pin "1") (pinfunction "1_1") (pintype "passive"))
      (node (ref "Z-MOT1") (pin "1") (pinfunction "1_1") (pintype "passive"))
    )
    (net (code "163") (name "Net-(U$5-SLEEP)") (class "Default")
      (node (ref "U$5") (pin "RST") (pinfunction "RST_RST") (pintype "input"))
      (node (ref "U$5") (pin "SLP") (pinfunction "SLEEP_SLP") (pintype "input"))
    )
    (net (code "164") (name "Net-(U$7-SLEEP)") (class "Default")
      (node (ref "U$7") (pin "RST") (pinfunction "RST_RST") (pintype "input"))
      (node (ref "U$7") (pin "SLP") (pinfunction "SLEEP_SLP") (pintype "input"))
    )
    (net (code "165") (name "Net-(U$8-SLEEP)") (class "Default")
      (node (ref "U$8") (pin "RST") (pinfunction "RST_RST") (pintype "input"))
      (node (ref "U$8") (pin "SLP") (pinfunction "SLEEP_SLP") (pintype "input"))
    )
    (net (code "166") (name "Net-(U$9-SLEEP)") (class "Default")
      (node (ref "U$9") (pin "RST") (pinfunction "RST_RST") (pintype "input"))
      (node (ref "U$9") (pin "SLP") (pinfunction "SLEEP_SLP") (pintype "input"))
    )
    (net (code "167") (name "Net-(U$10-SLEEP)") (class "Default")
      (node (ref "U$10") (pin "RST") (pinfunction "RST_RST") (pintype "input"))
      (node (ref "U$10") (pin "SLP") (pinfunction "SLEEP_SLP") (pintype "input"))
    )
    (net (code "168") (name "Net-(X-MOT-Pad1)") (class "Default")
      (node (ref "X") (pin "2B") (pinfunction "2B_2B") (pintype "output"))
      (node (ref "X-MOT") (pin "1") (pinfunction "1_1") (pintype "passive"))
    )
    (net (code "169") (name "Net-(X-MOT-Pad2)") (class "Default")
      (node (ref "X") (pin "2A") (pinfunction "2A_2A") (pintype "output"))
      (node (ref "X-MOT") (pin "2") (pinfunction "2_2") (pintype "passive"))
    )
    (net (code "170") (name "Net-(X-MOT-Pad3)") (class "Default")
      (node (ref "X") (pin "1A") (pinfunction "1A_1A") (pintype "output"))
      (node (ref "X-MOT") (pin "3") (pinfunction "3_3") (pintype "passive"))
    )
    (net (code "171") (name "Net-(X-MOT-Pad4)") (class "Default")
      (node (ref "X") (pin "1B") (pinfunction "1B_1B") (pintype "output"))
      (node (ref "X-MOT") (pin "4") (pinfunction "4_4") (pintype "passive"))
    )
    (net (code "172") (name "Net-(X-SLEEP)") (class "Default")
      (node (ref "X") (pin "RST") (pinfunction "RST_RST") (pintype "input"))
      (node (ref "X") (pin "SLP") (pinfunction "SLEEP_SLP") (pintype "input"))
    )
    (net (code "173") (name "VCC") (class "Default")
      (node (ref "AUX1") (pin "1") (pinfunction "1_1") (pintype "passive"))
      (node (ref "AUX1") (pin "2") (pinfunction "2_2") (pintype "passive"))
      (node (ref "AUX2") (pin "1") (pinfunction "1_1") (pintype "passive"))
      (node (ref "C17") (pin "+") (pinfunction "+_+") (pintype "passive"))
      (node (ref "C4") (pin "+") (pinfunction "+_+") (pintype "passive"))
      (node (ref "C6") (pin "+") (pinfunction "+_+") (pintype "passive"))
      (node (ref "D1") (pin "2") (pinfunction "-_2") (pintype "passive"))
      (node (ref "D10") (pin "2") (pinfunction "-_2") (pintype "passive"))
      (node (ref "D2") (pin "2") (pinfunction "-_2") (pintype "passive"))
      (node (ref "D5") (pin "2") (pinfunction "-_2") (pintype "passive"))
      (node (ref "D7") (pin "1") (pinfunction "+_1") (pintype "passive"))
      (node (ref "F1") (pin "2") (pinfunction "2_2") (pintype "passive"))
      (node (ref "I2C") (pin "1") (pinfunction "1_1") (pintype "passive"))
      (node (ref "IC2") (pin "1") (pinfunction "IN_1") (pintype "input"))
      (node (ref "IC3") (pin "32") (pinfunction "AVCC_32") (pintype "bidirectional"))
      (node (ref "IC3") (pin "4") (pinfunction "VCC_4") (pintype "bidirectional"))
      (node (ref "JP1") (pin "10") (pinfunction "10_10") (pintype "passive"))
      (node (ref "JP2") (pin "5") (pinfunction "5_5") (pintype "passive"))
      (node (ref "JP3") (pin "15") (pinfunction "15_15") (pintype "passive"))
      (node (ref "JP4") (pin "26") (pinfunction "26_26") (pintype "passive"))
      (node (ref "JP4") (pin "6") (pinfunction "6_6") (pintype "passive"))
      (node (ref "JP5") (pin "2") (pinfunction "2_2") (pintype "passive"))
      (node (ref "L4") (pin "2") (pinfunction "2_2") (pintype "passive"))
      (node (ref "POWER") (pin "+") (pinfunction "+_+") (pintype "passive"))
      (node (ref "R10") (pin "2") (pinfunction "2_2") (pintype "passive"))
      (node (ref "R16") (pin "2") (pinfunction "2_2") (pintype "passive"))
      (node (ref "R2") (pin "2") (pinfunction "2_2") (pintype "passive"))
      (node (ref "R27") (pin "2") (pinfunction "2_2") (pintype "passive"))
      (node (ref "R3") (pin "2") (pinfunction "2_2") (pintype "passive"))
      (node (ref "R30") (pin "1") (pinfunction "1_1") (pintype "passive"))
      (node (ref "R31") (pin "1") (pinfunction "1_1") (pintype "passive"))
      (node (ref "R33") (pin "2") (pinfunction "2_2") (pintype "passive"))
      (node (ref "R36") (pin "2") (pinfunction "2_2") (pintype "passive"))
      (node (ref "R4") (pin "2") (pinfunction "2_2") (pintype "passive"))
      (node (ref "R43") (pin "2") (pinfunction "2_2") (pintype "passive"))
      (node (ref "R45") (pin "2") (pinfunction "2_2") (pintype "passive"))
      (node (ref "R46") (pin "2") (pinfunction "2_2") (pintype "passive"))
      (node (ref "R49") (pin "2") (pinfunction "2_2") (pintype "passive"))
      (node (ref "R5") (pin "2") (pinfunction "2_2") (pintype "passive"))
      (node (ref "R51") (pin "2") (pinfunction "2_2") (pintype "passive"))
      (node (ref "R52") (pin "2") (pinfunction "2_2") (pintype "passive"))
      (node (ref "R6") (pin "2") (pinfunction "2_2") (pintype "passive"))
      (node (ref "R8") (pin "2") (pinfunction "2_2") (pintype "passive"))
      (node (ref "S10") (pin "4") (pinfunction "4_4") (pintype "passive"))
      (node (ref "S10") (pin "5") (pinfunction "5_5") (pintype "passive"))
      (node (ref "S10") (pin "6") (pinfunction "6_6") (pintype "passive"))
      (node (ref "S2") (pin "4") (pinfunction "4_4") (pintype "passive"))
      (node (ref "S2") (pin "5") (pinfunction "5_5") (pintype "passive"))
      (node (ref "S2") (pin "6") (pinfunction "6_6") (pintype "passive"))
      (node (ref "S3") (pin "4") (pinfunction "4_4") (pintype "passive"))
      (node (ref "S3") (pin "5") (pinfunction "5_5") (pintype "passive"))
      (node (ref "S3") (pin "6") (pinfunction "6_6") (pintype "passive"))
      (node (ref "S4") (pin "4") (pinfunction "4_4") (pintype "passive"))
      (node (ref "S4") (pin "5") (pinfunction "5_5") (pintype "passive"))
      (node (ref "S4") (pin "6") (pinfunction "6_6") (pintype "passive"))
      (node (ref "S5") (pin "4") (pinfunction "4_4") (pintype "passive"))
      (node (ref "S5") (pin "5") (pinfunction "5_5") (pintype "passive"))
      (node (ref "S5") (pin "6") (pinfunction "6_6") (pintype "passive"))
      (node (ref "S6") (pin "4") (pinfunction "4_4") (pintype "passive"))
      (node (ref "S6") (pin "5") (pinfunction "5_5") (pintype "passive"))
      (node (ref "S6") (pin "6") (pinfunction "6_6") (pintype "passive"))
      (node (ref "S7") (pin "4") (pinfunction "4_4") (pintype "passive"))
      (node (ref "S7") (pin "5") (pinfunction "5_5") (pintype "passive"))
      (node (ref "S7") (pin "6") (pinfunction "6_6") (pintype "passive"))
      (node (ref "S8") (pin "4") (pinfunction "4_4") (pintype "passive"))
      (node (ref "S8") (pin "5") (pinfunction "5_5") (pintype "passive"))
      (node (ref "S8") (pin "6") (pinfunction "6_6") (pintype "passive"))
      (node (ref "S9") (pin "4") (pinfunction "4_4") (pintype "passive"))
      (node (ref "S9") (pin "5") (pinfunction "5_5") (pintype "passive"))
      (node (ref "S9") (pin "6") (pinfunction "6_6") (pintype "passive"))
      (node (ref "U$1") (pin "VDD") (pinfunction "VDD_VDD") (pintype "power_in"))
      (node (ref "U$10") (pin "VDD") (pinfunction "VDD_VDD") (pintype "power_in"))
      (node (ref "U$2") (pin "VDD") (pinfunction "VDD_VDD") (pintype "power_in"))
      (node (ref "U$4") (pin "VDD") (pinfunction "VDD_VDD") (pintype "power_in"))
      (node (ref "U$5") (pin "VDD") (pinfunction "VDD_VDD") (pintype "power_in"))
      (node (ref "U$7") (pin "VDD") (pinfunction "VDD_VDD") (pintype "power_in"))
      (node (ref "U$8") (pin "VDD") (pinfunction "VDD_VDD") (pintype "power_in"))
      (node (ref "U$9") (pin "VDD") (pinfunction "VDD_VDD") (pintype "power_in"))
      (node (ref "X") (pin "VDD") (pinfunction "VDD_VDD") (pintype "power_in"))
      (node (ref "X+") (pin "3") (pinfunction "3_3") (pintype "passive"))
      (node (ref "X-") (pin "3") (pinfunction "3_3") (pintype "passive"))
      (node (ref "Y+") (pin "3") (pinfunction "3_3") (pintype "passive"))
      (node (ref "Y-") (pin "3") (pinfunction "3_3") (pintype "passive"))
      (node (ref "Z+") (pin "3") (pinfunction "3_3") (pintype "passive"))
      (node (ref "Z-") (pin "3") (pinfunction "3_3") (pintype "passive"))
    )
    (net (code "174") (name "VCC1") (class "Default")
      (node (ref "HE0") (pin "P2") (pinfunction "2_P2") (pintype "passive"))
      (node (ref "HE1") (pin "P2") (pinfunction "2_P2") (pintype "passive"))
      (node (ref "PWRF0") (pin "1") (pinfunction "1_1") (pintype "passive"))
      (node (ref "PWRF1") (pin "1") (pinfunction "1_1") (pintype "passive"))
    )
    (net (code "175") (name "unconnected-(AUX2-Pad8)") (class "Default")
      (node (ref "AUX2") (pin "8") (pinfunction "8_8") (pintype "passive"))
    )
    (net (code "176") (name "unconnected-(IC3-PB4(T1{slash}PCINT4)-Pad18)") (class "Default")
      (node (ref "IC3") (pin "18") (pinfunction "PB4(T1/PCINT4)_18") (pintype "bidirectional"))
    )
    (net (code "177") (name "unconnected-(IC3-PB5(PCINT5)-Pad19)") (class "Default")
      (node (ref "IC3") (pin "19") (pinfunction "PB5(PCINT5)_19") (pintype "bidirectional"))
    )
    (net (code "178") (name "unconnected-(IC3-PB6(PCINT6)-Pad20)") (class "Default")
      (node (ref "IC3") (pin "20") (pinfunction "PB6(PCINT6)_20") (pintype "bidirectional"))
    )
    (net (code "179") (name "unconnected-(IC3-PB7(OC0A{slash}OC1C{slash}PCINT7)-Pad21)") (class "Default")
      (node (ref "IC3") (pin "21") (pinfunction "PB7(OC0A/OC1C/PCINT7)_21") (pintype "bidirectional"))
    )
    (net (code "180") (name "unconnected-(IC3-PC2(AIN2{slash}PCIN11)-Pad5)") (class "Default")
      (node (ref "IC3") (pin "5") (pinfunction "PC2(AIN2/PCIN11)_5") (pintype "bidirectional"))
    )
    (net (code "181") (name "unconnected-(IC3-PC4(PCINT10)-Pad26)") (class "Default")
      (node (ref "IC3") (pin "26") (pinfunction "PC4(PCINT10)_26") (pintype "bidirectional"))
    )
    (net (code "182") (name "unconnected-(IC3-PC5(OC1B{slash}PCINT9)-Pad25)") (class "Default")
      (node (ref "IC3") (pin "25") (pinfunction "PC5(OC1B/PCINT9)_25") (pintype "bidirectional"))
    )
    (net (code "183") (name "unconnected-(IC3-PC6(OC1A{slash}PCINT8)-Pad23)") (class "Default")
      (node (ref "IC3") (pin "23") (pinfunction "PC6(OC1A/PCINT8)_23") (pintype "bidirectional"))
    )
    (net (code "184") (name "unconnected-(IC3-PC7(ICP1{slash}INT4{slash}CLKO)-Pad22)") (class "Default")
      (node (ref "IC3") (pin "22") (pinfunction "PC7(ICP1/INT4/CLKO)_22") (pintype "bidirectional"))
    )
    (net (code "185") (name "unconnected-(IC3-PD0(INT0{slash}OC0B)-Pad6)") (class "Default")
      (node (ref "IC3") (pin "6") (pinfunction "PD0(INT0/OC0B)_6") (pintype "bidirectional"))
    )
    (net (code "186") (name "unconnected-(IC3-PD1(INT1{slash}AIN0)-Pad7)") (class "Default")
      (node (ref "IC3") (pin "7") (pinfunction "PD1(INT1/AIN0)_7") (pintype "bidirectional"))
    )
    (net (code "187") (name "unconnected-(IC3-PD6(INT6{slash}AIN5{slash}RTS)-Pad12)") (class "Default")
      (node (ref "IC3") (pin "12") (pinfunction "PD6(INT6/AIN5/RTS)_12") (pintype "bidirectional"))
    )
    (net (code "188") (name "unconnected-(IC3-PD7(INT7{slash}HWB{slash}AIN6{slash}T0)-Pad13)") (class "Default")
      (node (ref "IC3") (pin "13") (pinfunction "PD7(INT7/HWB/AIN6/T0)_13") (pintype "bidirectional"))
    )
    (net (code "189") (name "unconnected-(JP1-Pad1)") (class "Default")
      (node (ref "JP1") (pin "1") (pinfunction "1_1") (pintype "passive"))
    )
    (net (code "190") (name "unconnected-(JP1-Pad4)") (class "Default")
      (node (ref "JP1") (pin "4") (pinfunction "4_4") (pintype "passive"))
    )
    (net (code "191") (name "unconnected-(JP1-Pad8)") (class "Default")
      (node (ref "JP1") (pin "8") (pinfunction "8_8") (pintype "passive"))
    )
    (net (code "192") (name "unconnected-(JP1-Pad9)") (class "Default")
      (node (ref "JP1") (pin "9") (pinfunction "9_9") (pintype "passive"))
    )
    (net (code "193") (name "unconnected-(JP1-Pad14)") (class "Default")
      (node (ref "JP1") (pin "14") (pinfunction "14_14") (pintype "passive"))
    )
    (net (code "194") (name "unconnected-(JP1-Pad16)") (class "Default")
      (node (ref "JP1") (pin "16") (pinfunction "16_16") (pintype "passive"))
    )
    (net (code "195") (name "unconnected-(JP1-Pad19)") (class "Default")
      (node (ref "JP1") (pin "19") (pinfunction "19_19") (pintype "passive"))
    )
    (net (code "196") (name "unconnected-(JP1-Pad24)") (class "Default")
      (node (ref "JP1") (pin "24") (pinfunction "24_24") (pintype "passive"))
    )
    (net (code "197") (name "unconnected-(JP1-Pad26)") (class "Default")
      (node (ref "JP1") (pin "26") (pinfunction "26_26") (pintype "passive"))
    )
    (net (code "198") (name "unconnected-(JP2-Pad1)") (class "Default")
      (node (ref "JP2") (pin "1") (pinfunction "1_1") (pintype "passive"))
    )
    (net (code "199") (name "unconnected-(JP2-Pad3)") (class "Default")
      (node (ref "JP2") (pin "3") (pinfunction "3_3") (pintype "passive"))
    )
    (net (code "200") (name "unconnected-(JP2-Pad4)") (class "Default")
      (node (ref "JP2") (pin "4") (pinfunction "4_4") (pintype "passive"))
    )
    (net (code "201") (name "unconnected-(JP2-Pad14)") (class "Default")
      (node (ref "JP2") (pin "14") (pinfunction "14_14") (pintype "passive"))
    )
    (net (code "202") (name "unconnected-(JP2-Pad18)") (class "Default")
      (node (ref "JP2") (pin "18") (pinfunction "18_18") (pintype "passive"))
    )
    (net (code "203") (name "unconnected-(JP2-Pad19)") (class "Default")
      (node (ref "JP2") (pin "19") (pinfunction "19_19") (pintype "passive"))
    )
    (net (code "204") (name "unconnected-(JP2-Pad21)") (class "Default")
      (node (ref "JP2") (pin "21") (pinfunction "21_21") (pintype "passive"))
    )
    (net (code "205") (name "unconnected-(JP2-Pad22)") (class "Default")
      (node (ref "JP2") (pin "22") (pinfunction "22_22") (pintype "passive"))
    )
    (net (code "206") (name "unconnected-(JP2-Pad23)") (class "Default")
      (node (ref "JP2") (pin "23") (pinfunction "23_23") (pintype "passive"))
    )
    (net (code "207") (name "unconnected-(JP2-Pad24)") (class "Default")
      (node (ref "JP2") (pin "24") (pinfunction "24_24") (pintype "passive"))
    )
    (net (code "208") (name "unconnected-(JP2-Pad25)") (class "Default")
      (node (ref "JP2") (pin "25") (pinfunction "25_25") (pintype "passive"))
    )
    (net (code "209") (name "unconnected-(JP3-Pad2)") (class "Default")
      (node (ref "JP3") (pin "2") (pinfunction "2_2") (pintype "passive"))
    )
    (net (code "210") (name "unconnected-(JP3-Pad7)") (class "Default")
      (node (ref "JP3") (pin "7") (pinfunction "7_7") (pintype "passive"))
    )
    (net (code "211") (name "unconnected-(JP3-Pad8)") (class "Default")
      (node (ref "JP3") (pin "8") (pinfunction "8_8") (pintype "passive"))
    )
    (net (code "212") (name "unconnected-(JP3-Pad9)") (class "Default")
      (node (ref "JP3") (pin "9") (pinfunction "9_9") (pintype "passive"))
    )
    (net (code "213") (name "unconnected-(JP3-Pad10)") (class "Default")
      (node (ref "JP3") (pin "10") (pinfunction "10_10") (pintype "passive"))
    )
    (net (code "214") (name "unconnected-(JP3-Pad11)") (class "Default")
      (node (ref "JP3") (pin "11") (pinfunction "11_11") (pintype "passive"))
    )
    (net (code "215") (name "unconnected-(JP3-Pad12)") (class "Default")
      (node (ref "JP3") (pin "12") (pinfunction "12_12") (pintype "passive"))
    )
    (net (code "216") (name "unconnected-(JP3-Pad13)") (class "Default")
      (node (ref "JP3") (pin "13") (pinfunction "13_13") (pintype "passive"))
    )
    (net (code "217") (name "unconnected-(JP3-Pad14)") (class "Default")
      (node (ref "JP3") (pin "14") (pinfunction "14_14") (pintype "passive"))
    )
    (net (code "218") (name "unconnected-(JP3-Pad19)") (class "Default")
      (node (ref "JP3") (pin "19") (pinfunction "19_19") (pintype "passive"))
    )
    (net (code "219") (name "unconnected-(JP3-Pad23)") (class "Default")
      (node (ref "JP3") (pin "23") (pinfunction "23_23") (pintype "passive"))
    )
    (net (code "220") (name "unconnected-(JP4-Pad1)") (class "Default")
      (node (ref "JP4") (pin "1") (pinfunction "1_1") (pintype "passive"))
    )
    (net (code "221") (name "unconnected-(JP4-Pad2)") (class "Default")
      (node (ref "JP4") (pin "2") (pinfunction "2_2") (pintype "passive"))
    )
    (net (code "222") (name "unconnected-(JP4-Pad3)") (class "Default")
      (node (ref "JP4") (pin "3") (pinfunction "3_3") (pintype "passive"))
    )
    (net (code "223") (name "unconnected-(JP4-Pad4)") (class "Default")
      (node (ref "JP4") (pin "4") (pinfunction "4_4") (pintype "passive"))
    )
    (net (code "224") (name "unconnected-(JP4-Pad14)") (class "Default")
      (node (ref "JP4") (pin "14") (pinfunction "14_14") (pintype "passive"))
    )
    (net (code "225") (name "unconnected-(JP4-Pad20)") (class "Default")
      (node (ref "JP4") (pin "20") (pinfunction "20_20") (pintype "passive"))
    )
    (net (code "226") (name "unconnected-(JP4-Pad25)") (class "Default")
      (node (ref "JP4") (pin "25") (pinfunction "25_25") (pintype "passive"))
    )
  )
)
